# Bidirectional_Amp.net
KiCad netlist of a schematic drawn in EAGLE
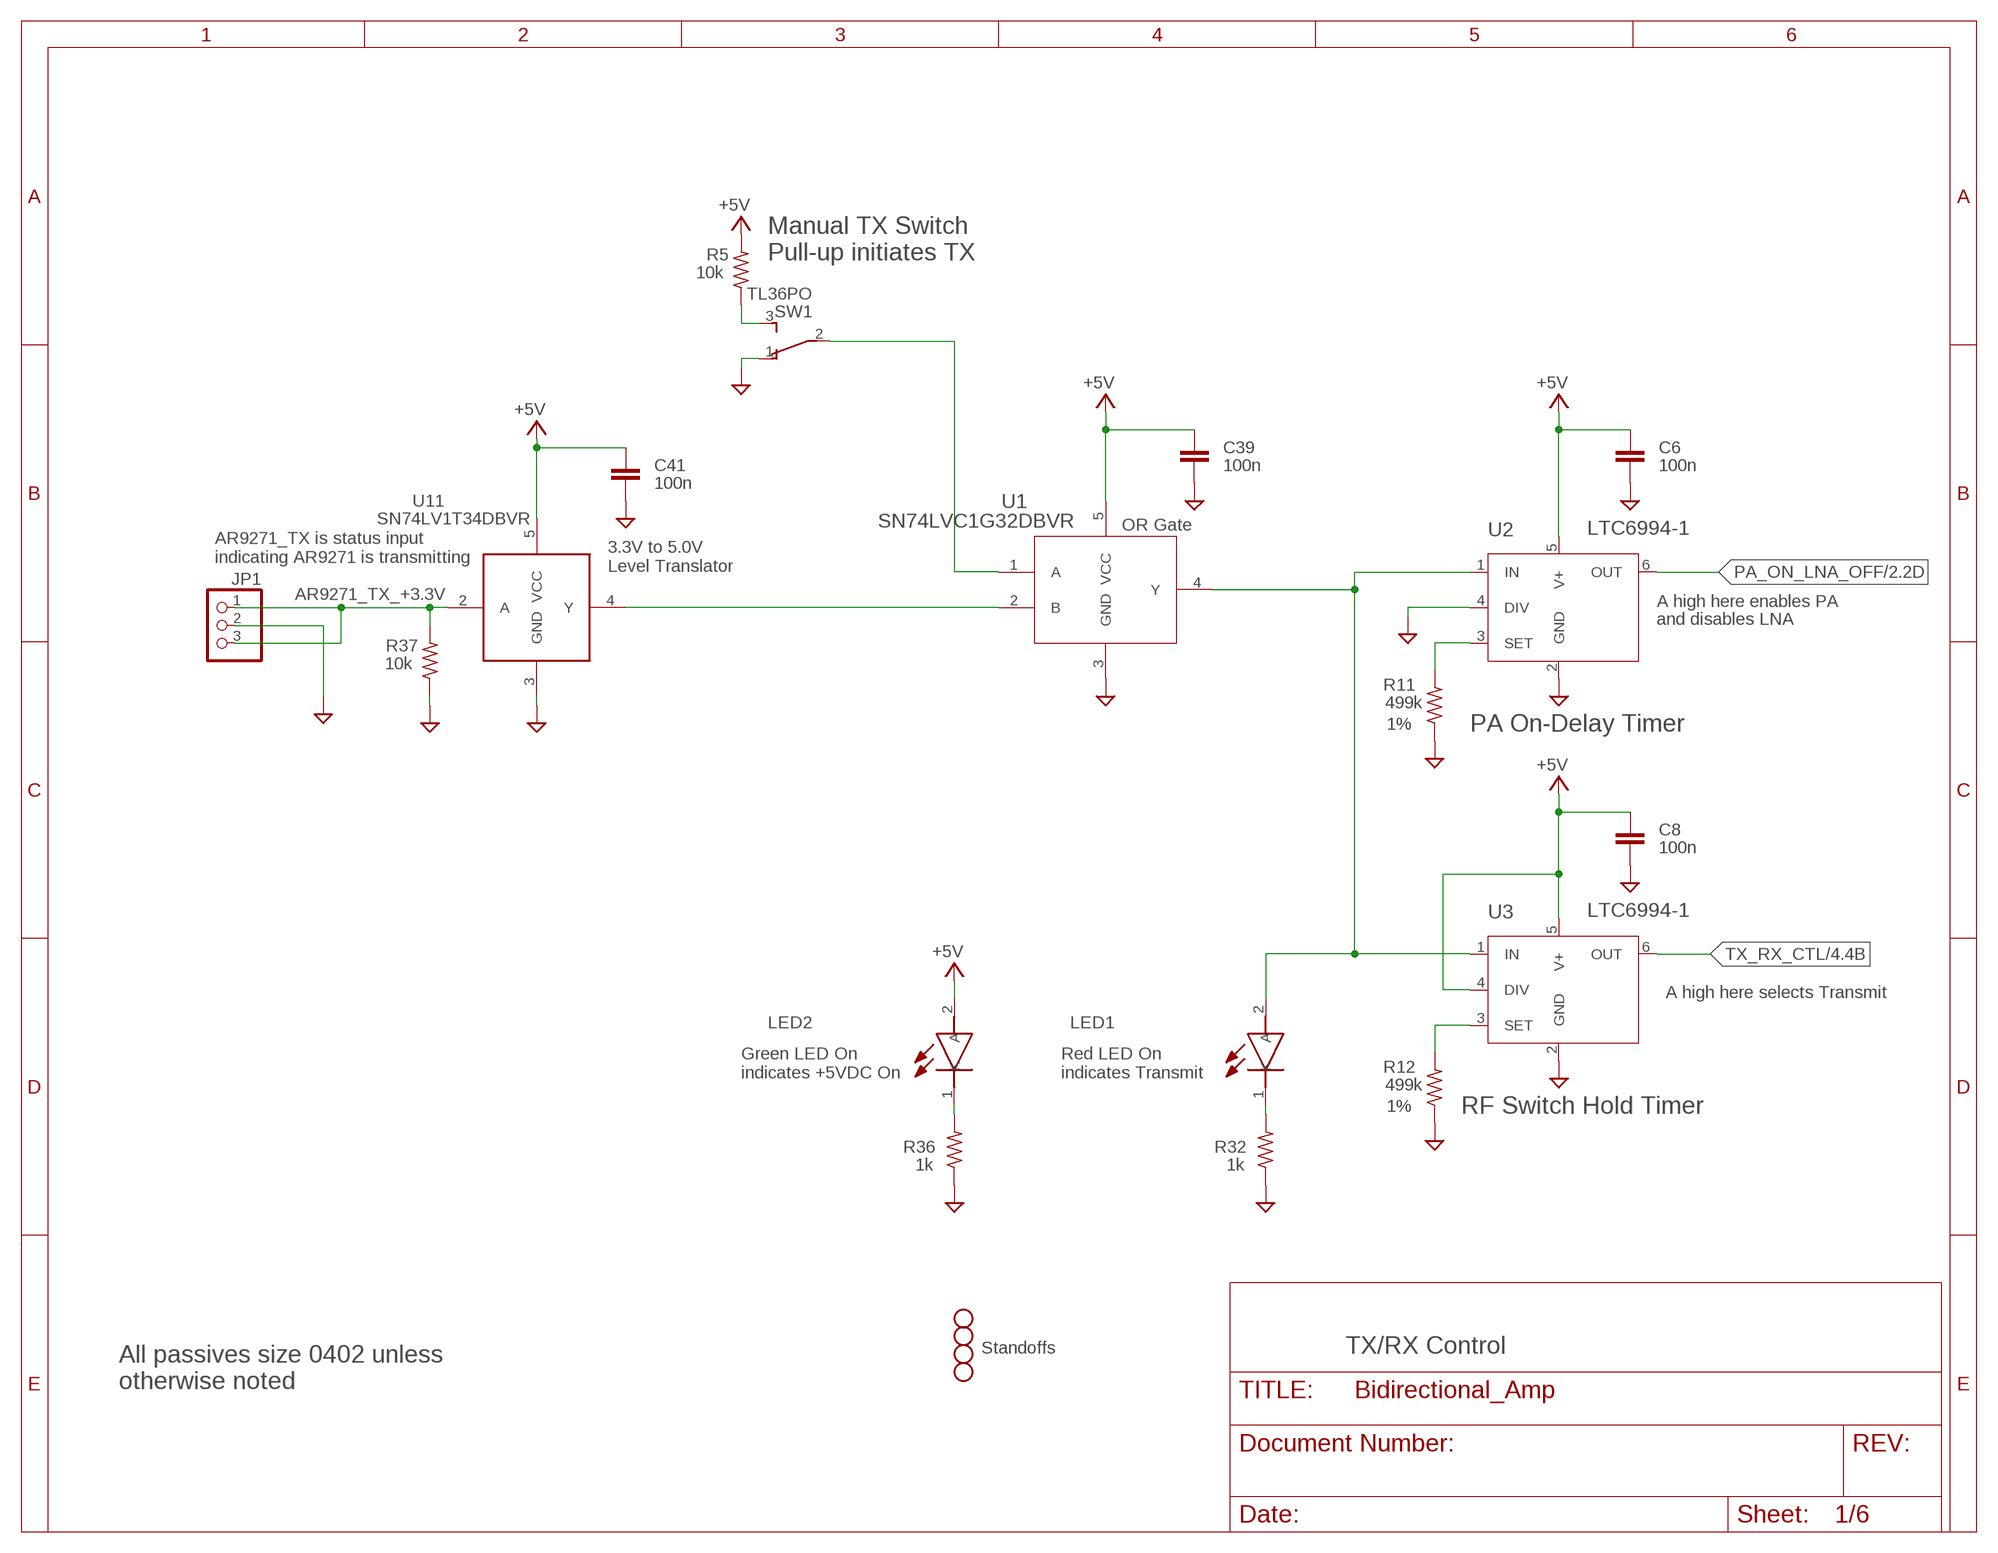
[diagram p0: schematic, sheet 1]
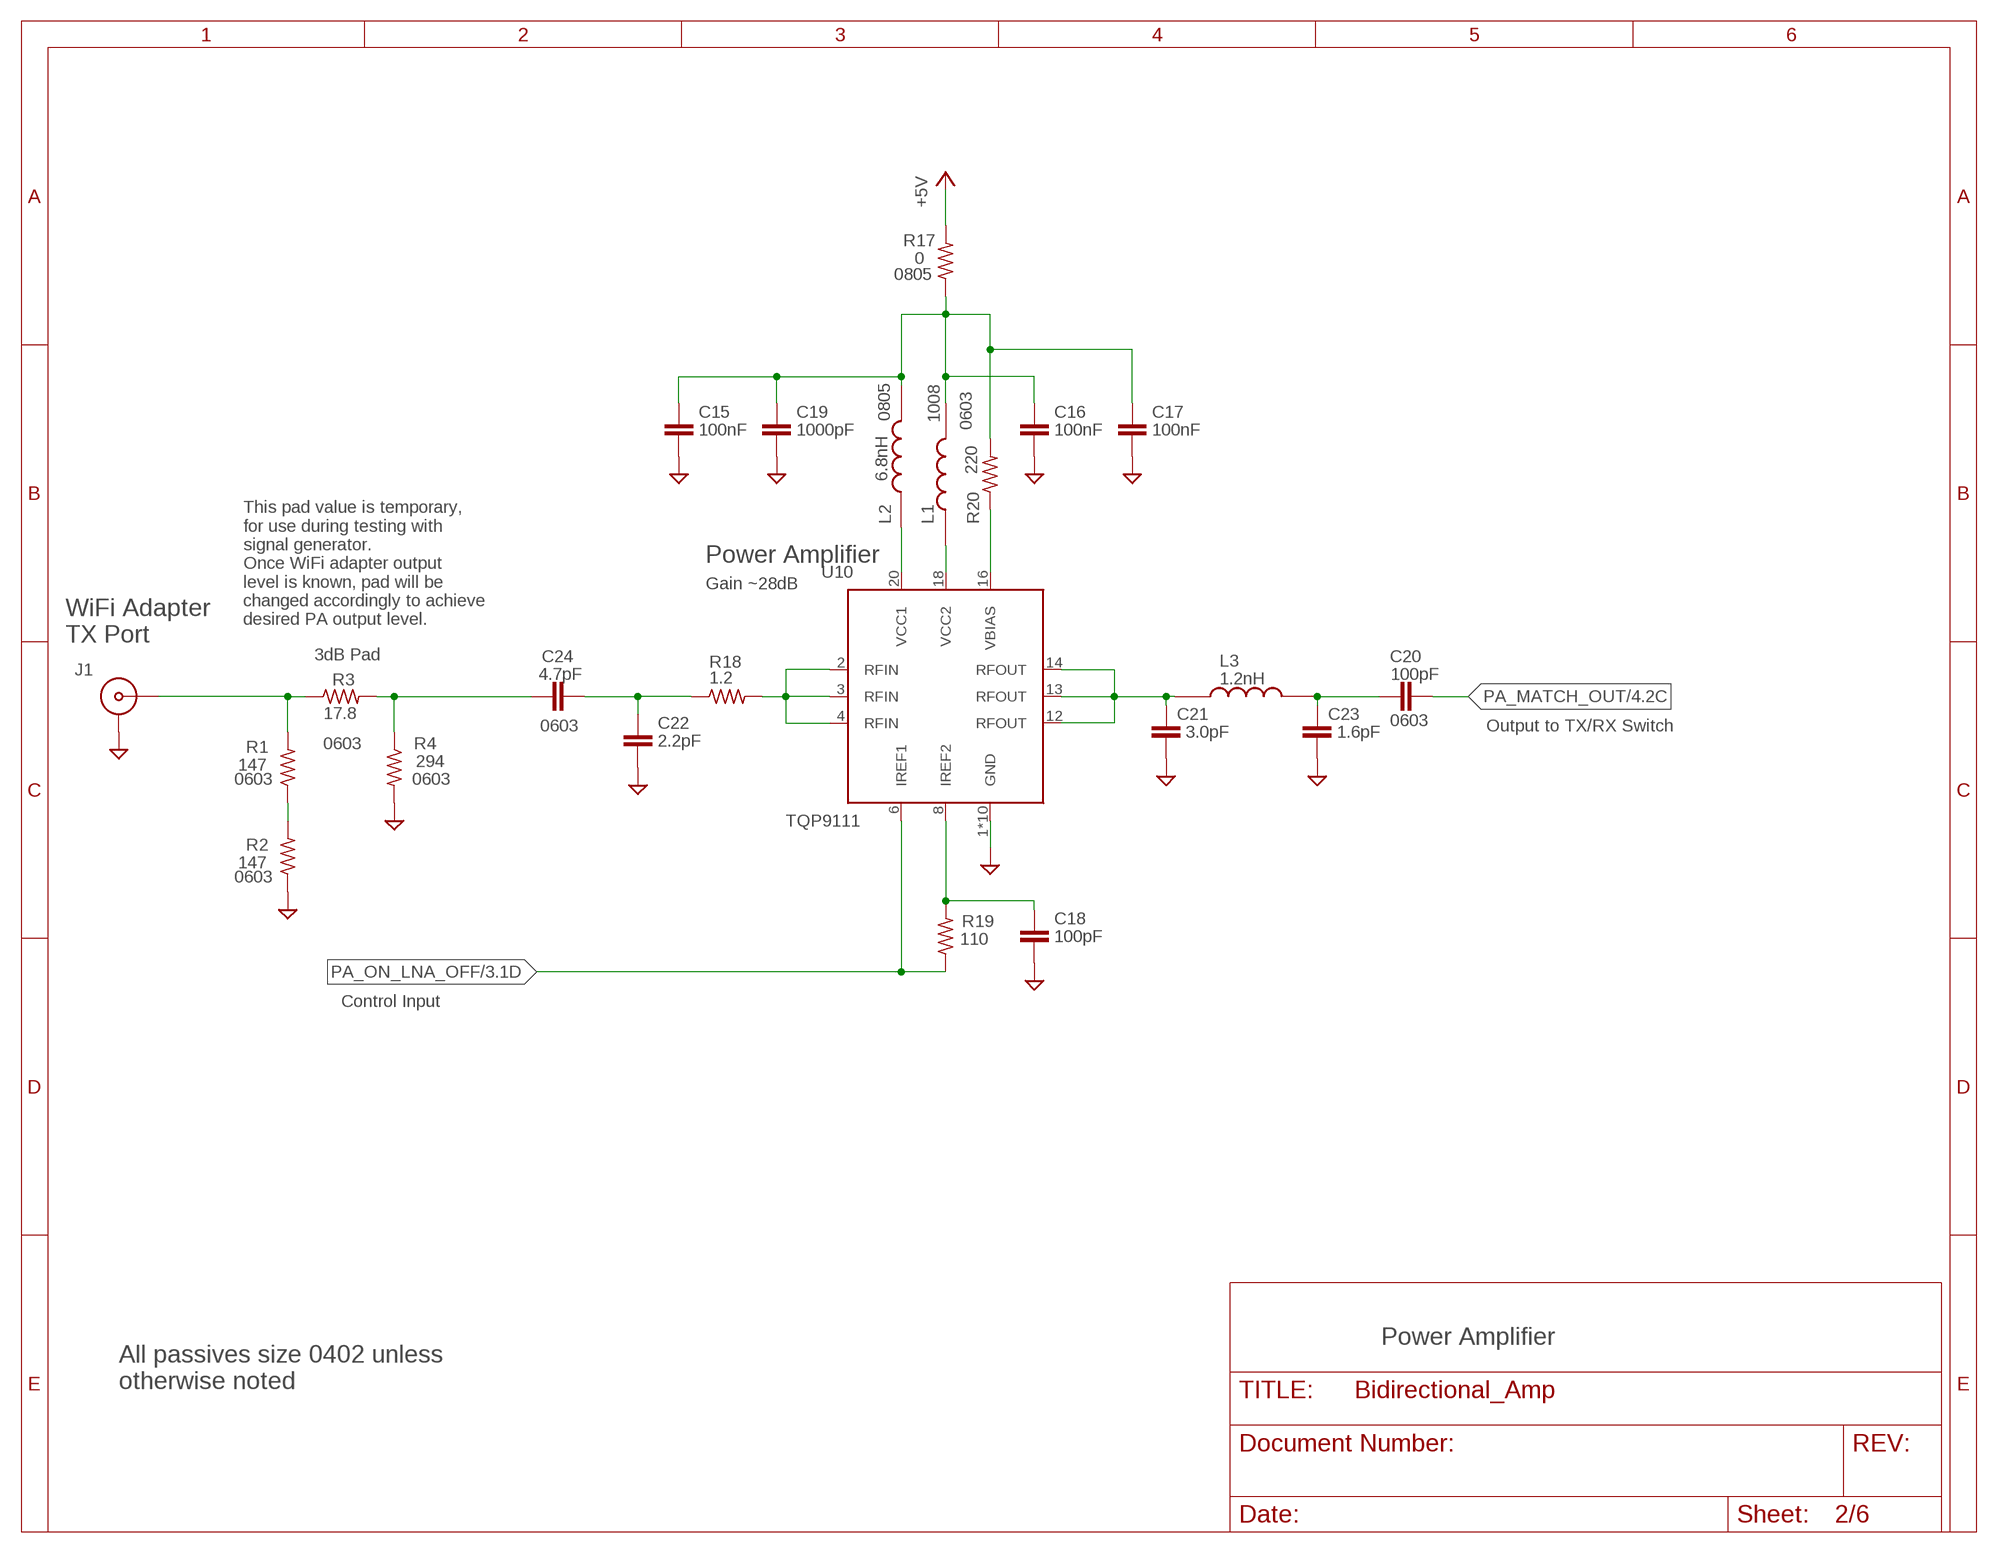
[diagram p1: schematic, sheet 2]
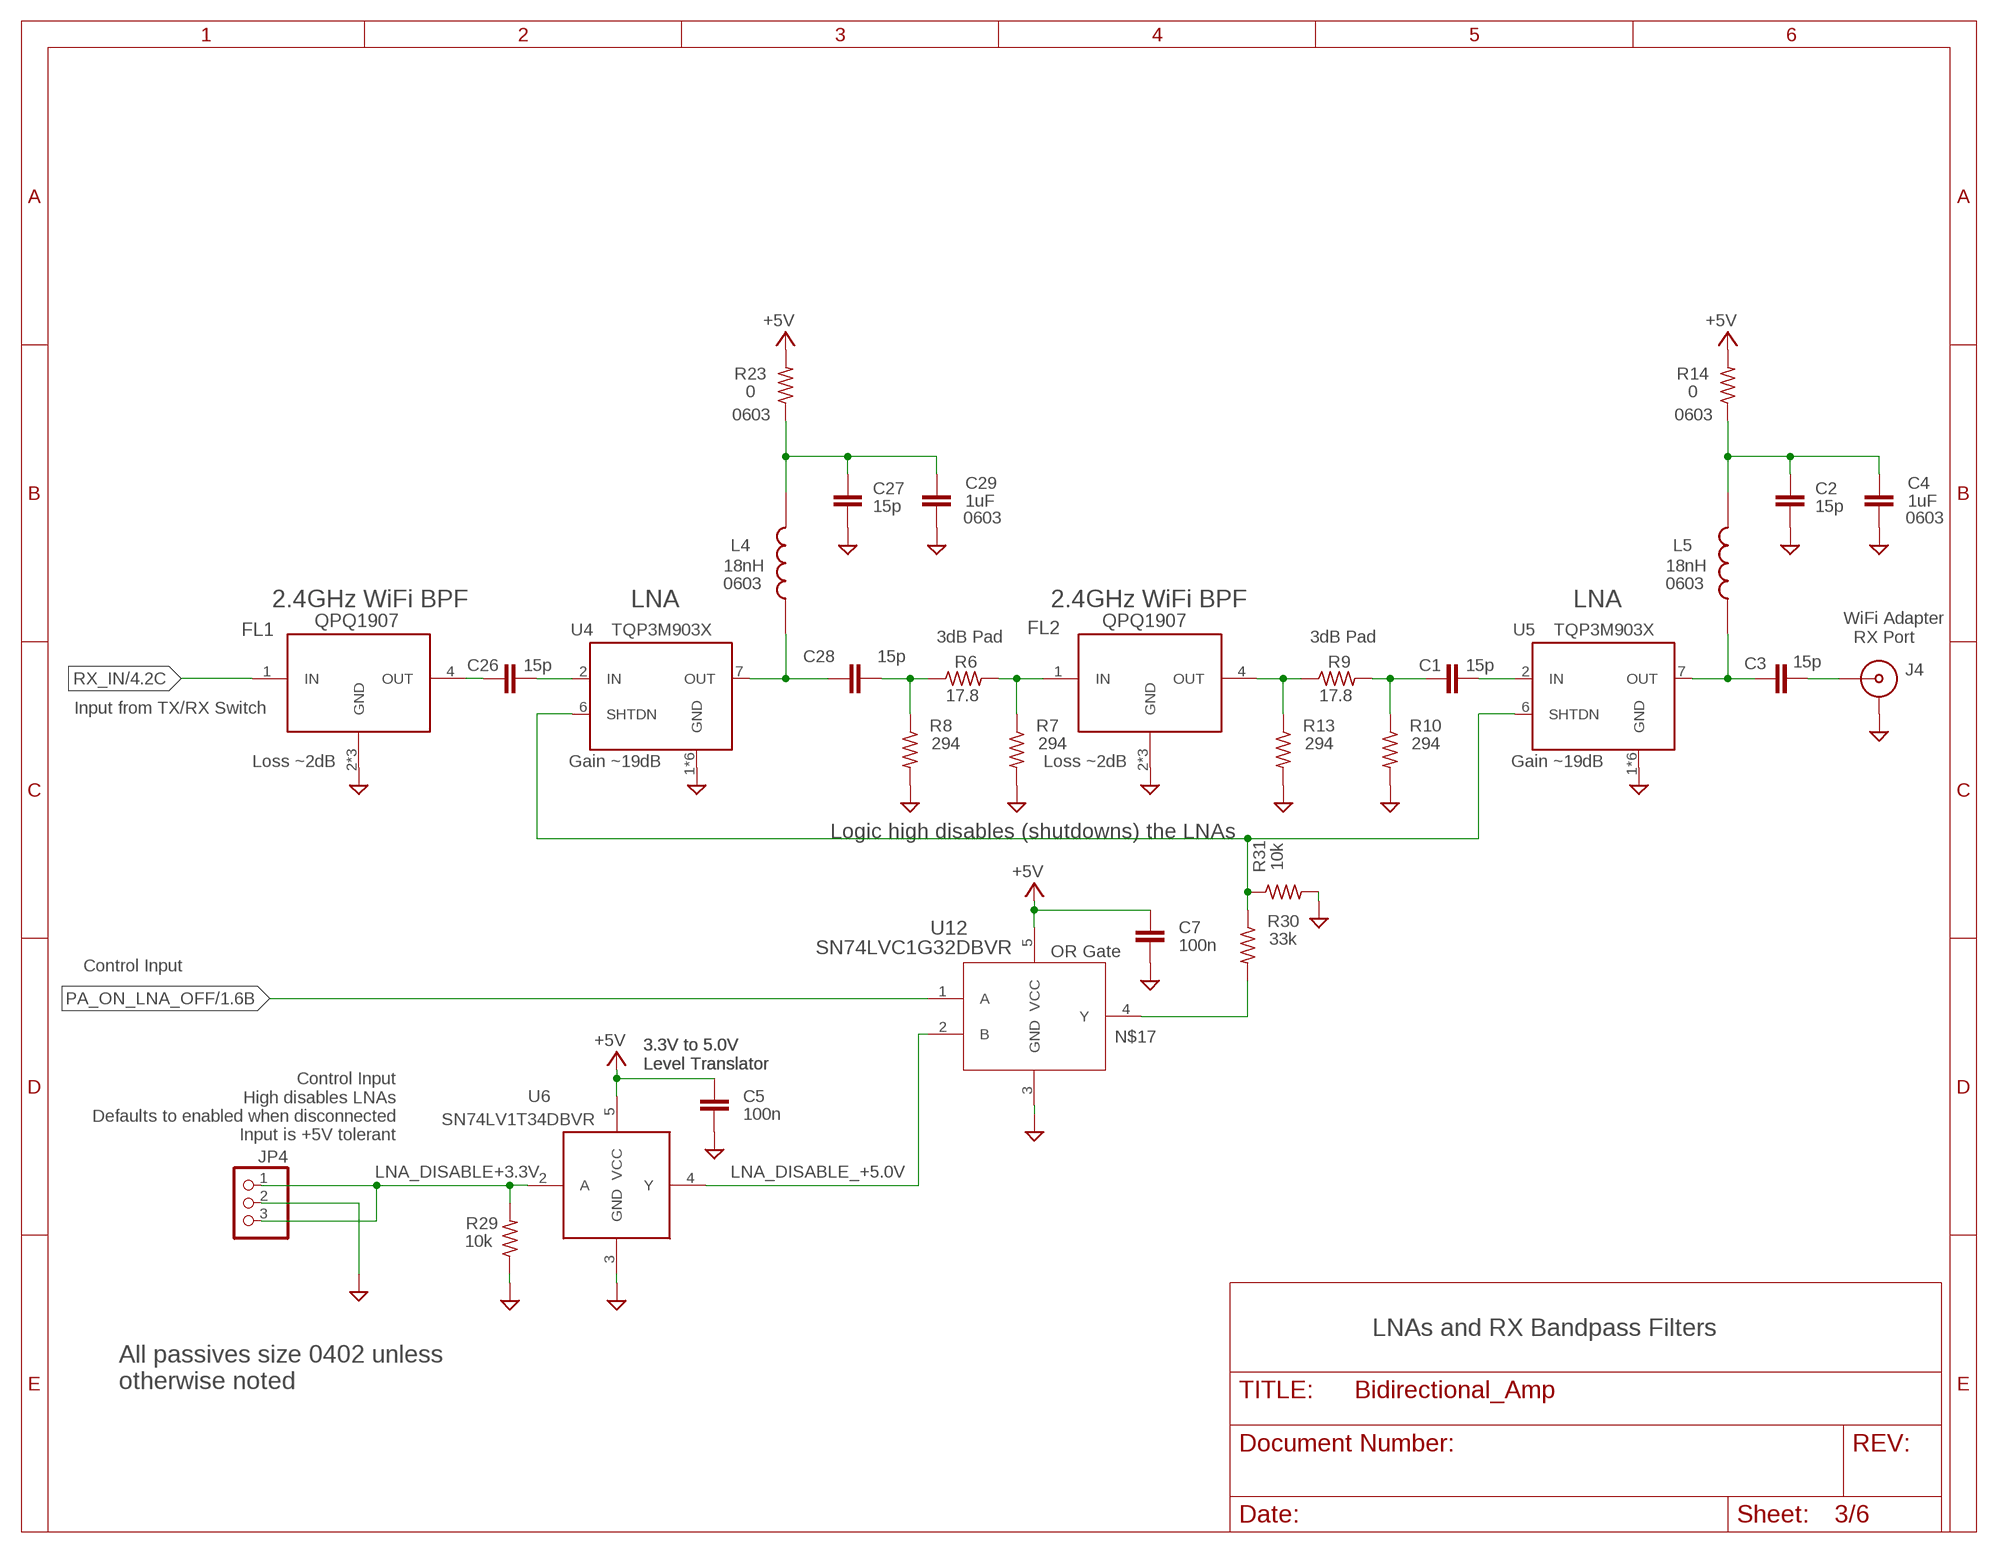
[diagram p2: schematic, sheet 3]
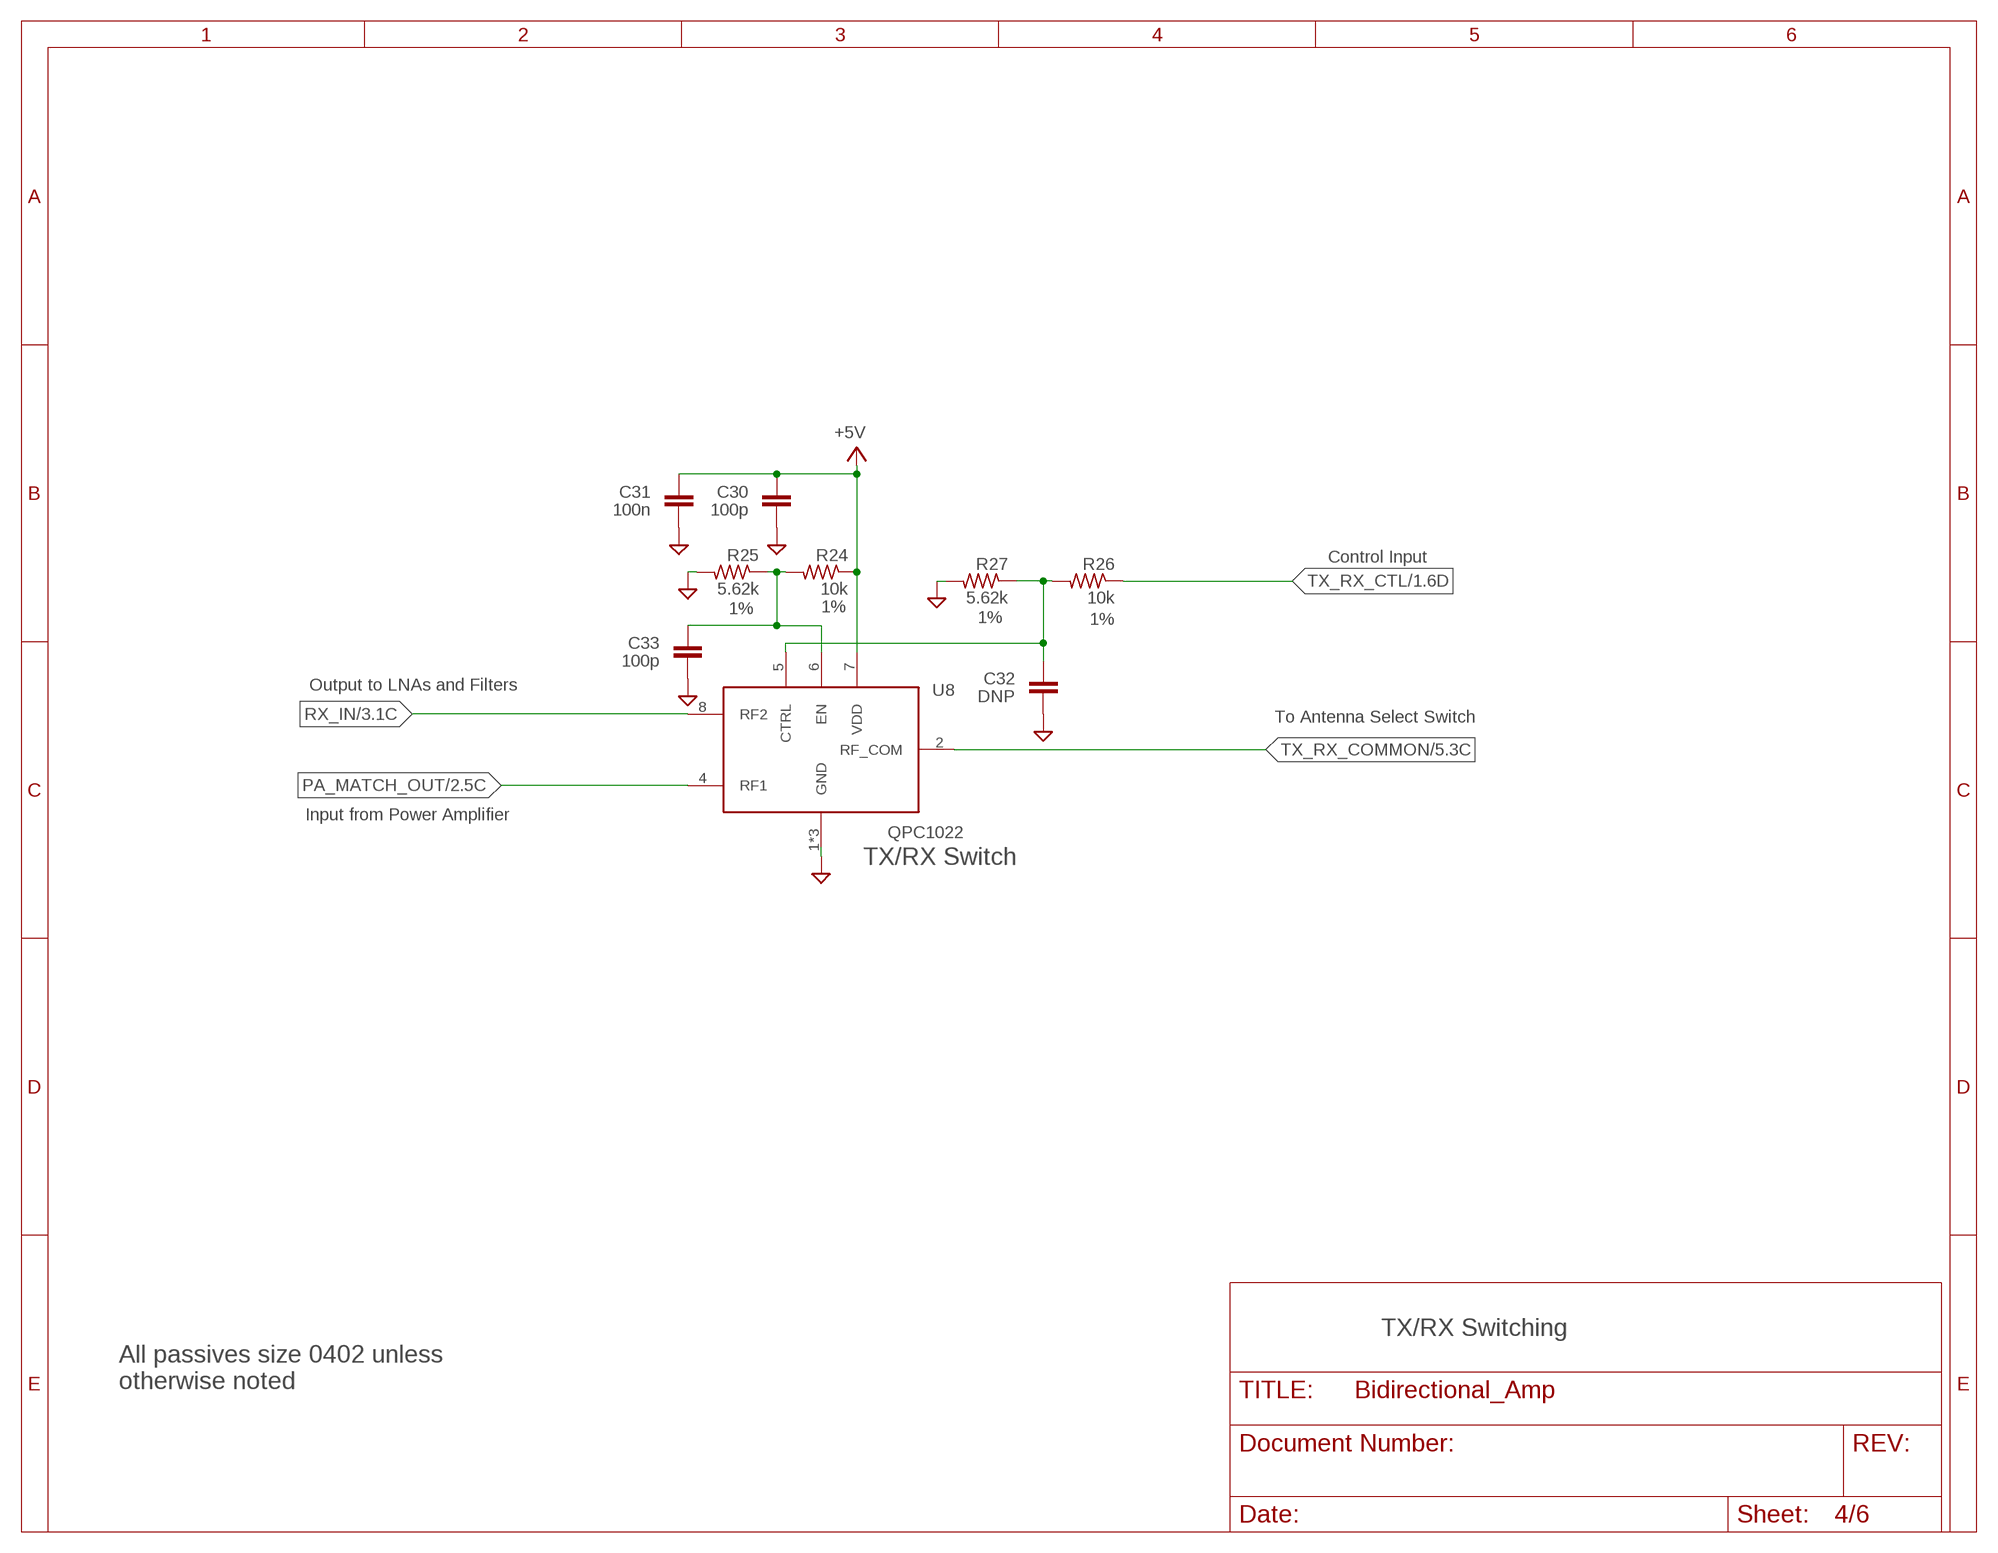
[diagram p3: schematic, sheet 4]
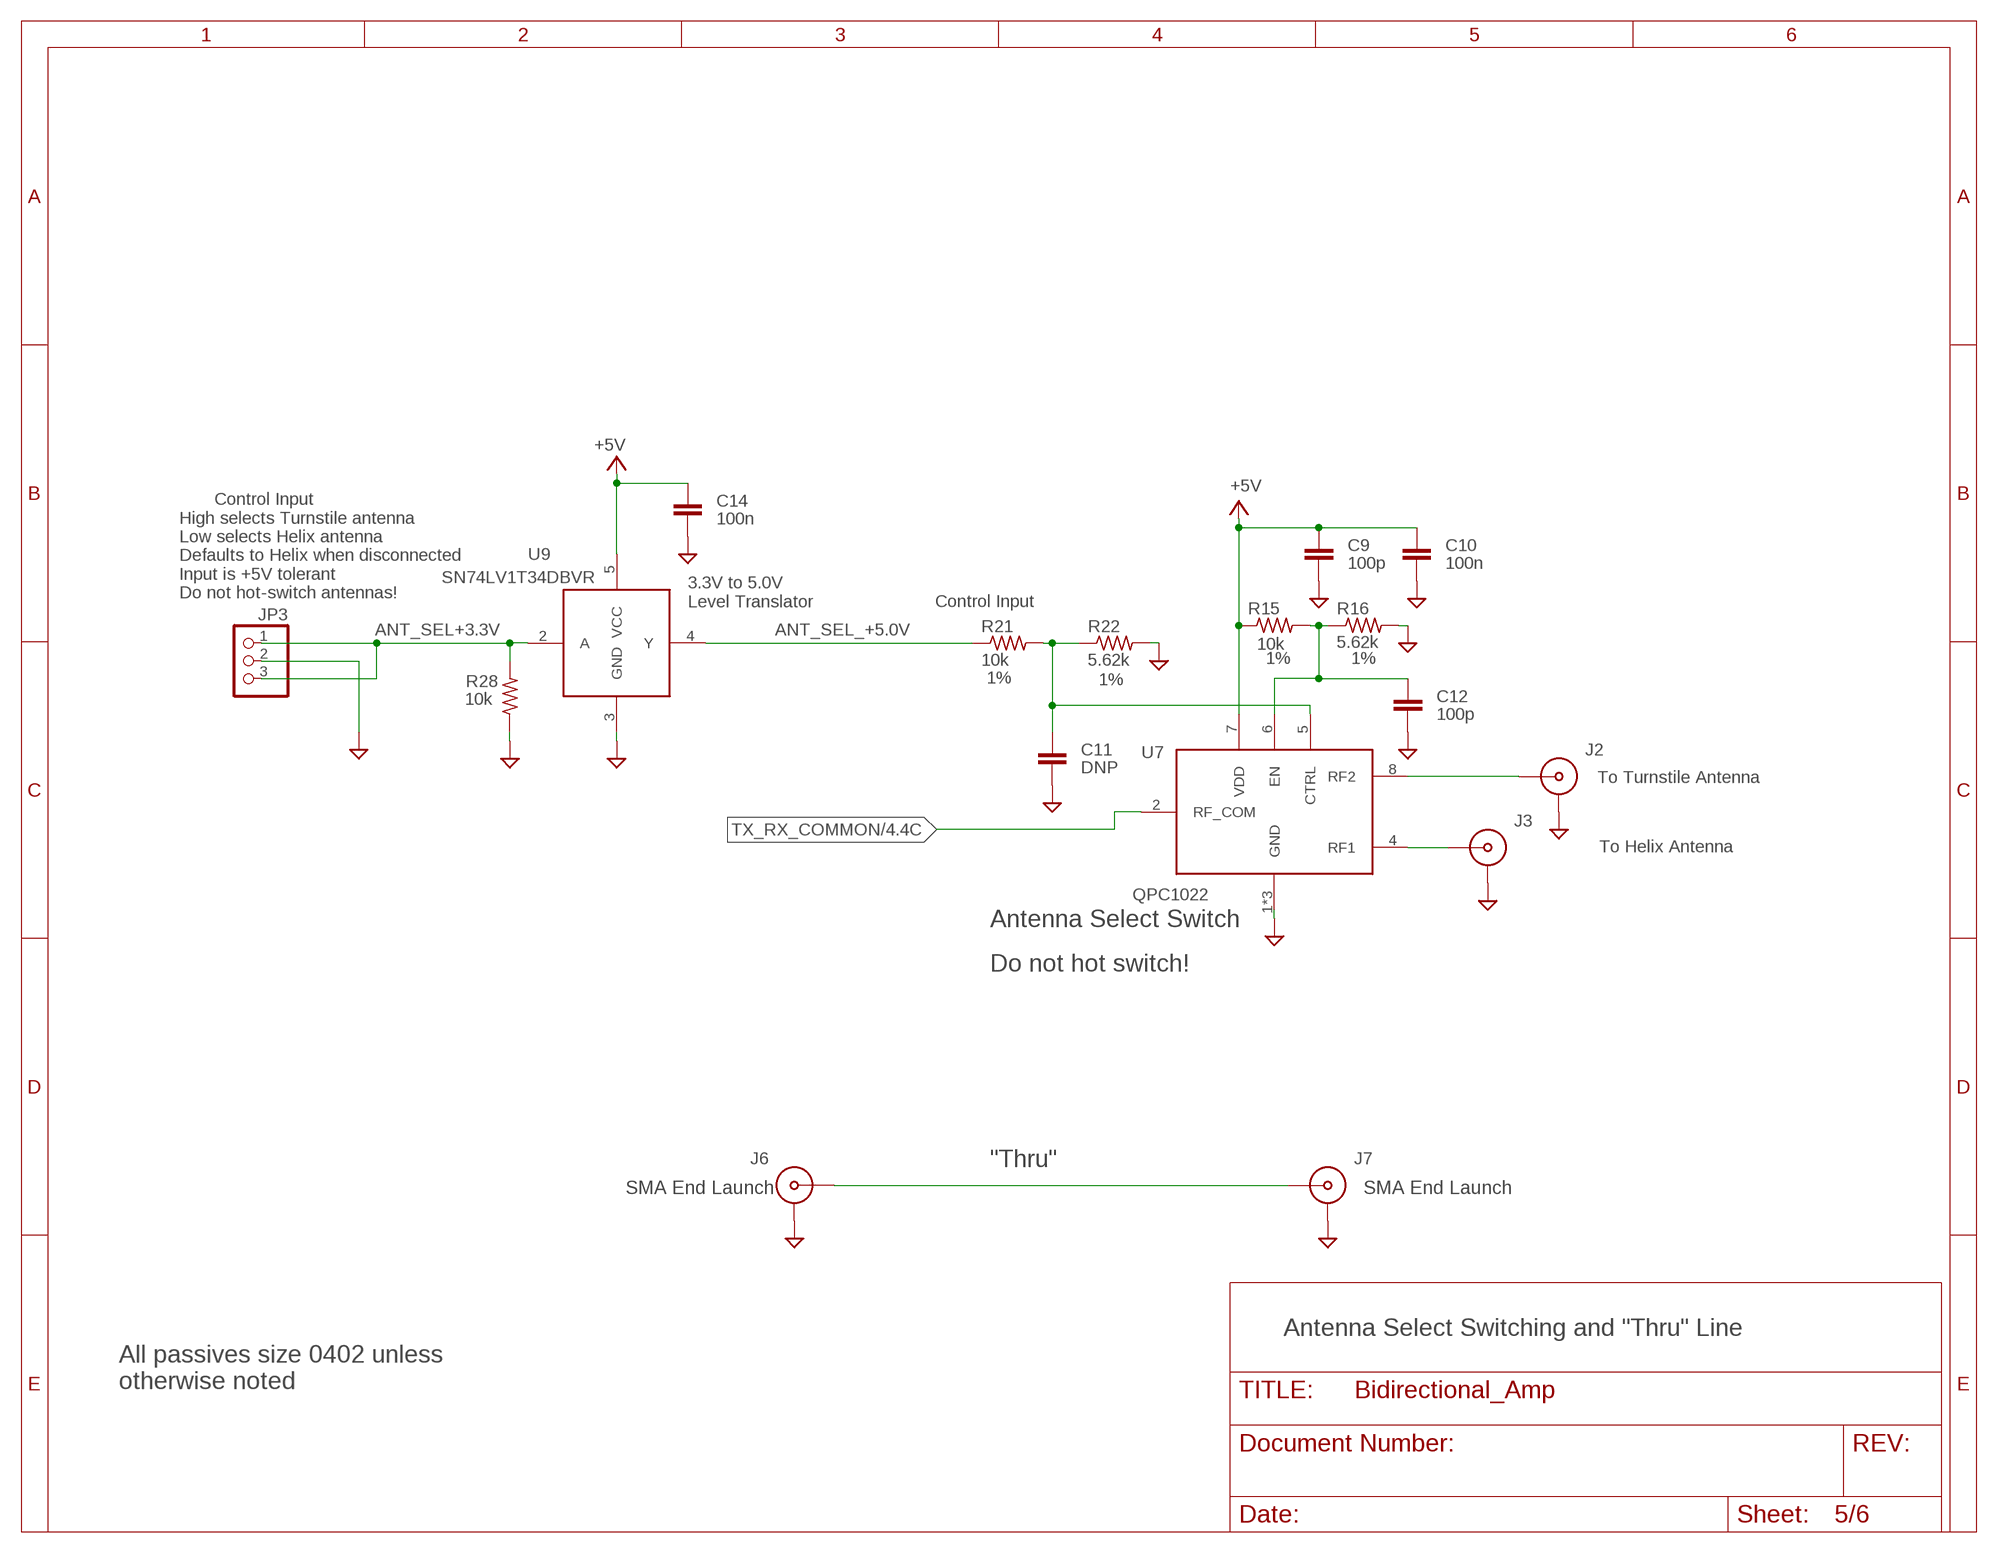
[diagram p4: schematic, sheet 5]
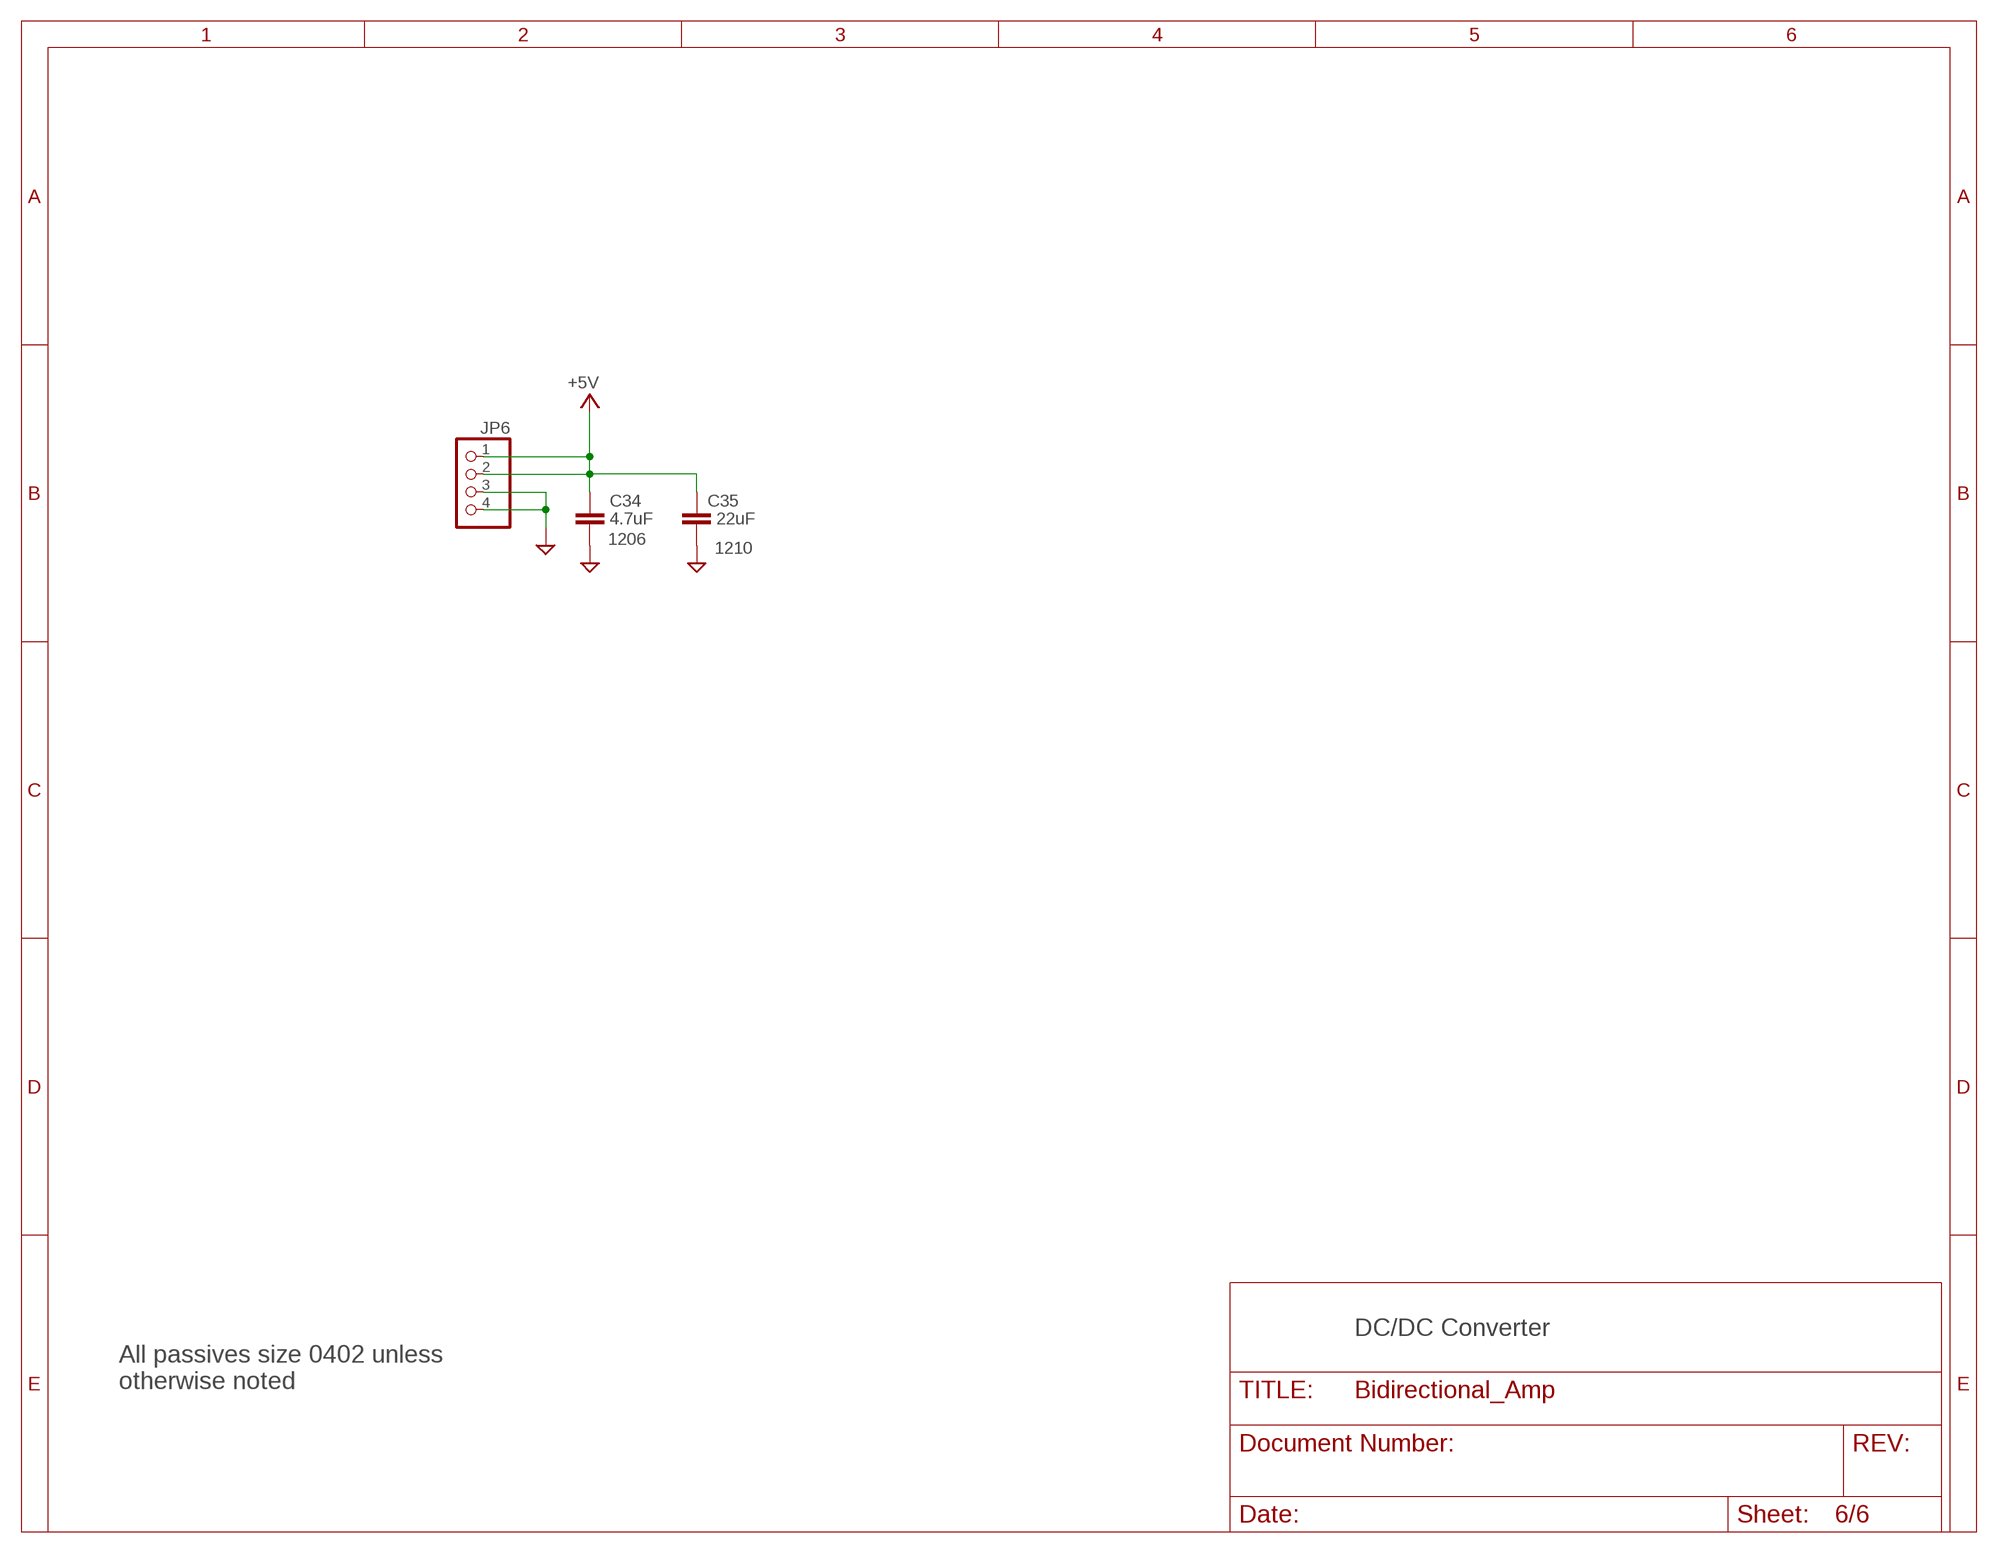
[diagram p5: schematic, sheet 6]

(export (version "E")
  (design (tool "Eeschema 10.0.6"))
  (components
    (comp (ref "C6")
      (value "100n")
      (footprint "eagle-import:.0402-B-NOSILK")
      (fields (field (name "MFR") "TDK") (field (name "MPN") "CGA2B1X7R1C104K050BC"))
      (libsource (lib "eagle-import") (part "C-EU0402-B-NOSILK"))
    )
    (comp (ref "C8")
      (value "100n")
      (footprint "eagle-import:.0402-B-NOSILK")
      (fields (field (name "MFR") "TDK") (field (name "MPN") "CGA2B1X7R1C104K050BC"))
      (libsource (lib "eagle-import") (part "C-EU0402-B-NOSILK"))
    )
    (comp (ref "C39")
      (value "100n")
      (footprint "eagle-import:.0402-B-NOSILK")
      (fields (field (name "MFR") "TDK") (field (name "MPN") "CGA2B1X7R1C104K050BC"))
      (libsource (lib "eagle-import") (part "C-EU0402-B-NOSILK"))
    )
    (comp (ref "C41")
      (value "100n")
      (footprint "eagle-import:.0402-B-NOSILK")
      (fields (field (name "MFR") "TDK") (field (name "MPN") "CGA2B1X7R1C104K050BC"))
      (libsource (lib "eagle-import") (part "C-EU0402-B-NOSILK"))
    )
    (comp (ref "H1")
      (value "STAND-OFFTIGHT")
      (footprint "eagle-import:STAND-OFF-TIGHT")
      (libsource (lib "eagle-import") (part "STAND-OFFTIGHT"))
    )
    (comp (ref "H2")
      (value "STAND-OFFTIGHT")
      (footprint "eagle-import:STAND-OFF-TIGHT")
      (libsource (lib "eagle-import") (part "STAND-OFFTIGHT"))
    )
    (comp (ref "H3")
      (value "STAND-OFFTIGHT")
      (footprint "eagle-import:STAND-OFF-TIGHT")
      (libsource (lib "eagle-import") (part "STAND-OFFTIGHT"))
    )
    (comp (ref "H4")
      (value "STAND-OFFTIGHT")
      (footprint "eagle-import:STAND-OFF-TIGHT")
      (libsource (lib "eagle-import") (part "STAND-OFFTIGHT"))
    )
    (comp (ref "JP1")
      (value "PINHD-1X3")
      (footprint "eagle-import:1X03")
      (fields (field (name "MFR") "Molex") (field (name "MPN") "22-23-2031"))
      (libsource (lib "eagle-import") (part "PINHD-1X3"))
    )
    (comp (ref "LED1")
      (value "LTST-C193KRKT-5A")
      (footprint "eagle-import:LEDC1607X80N")
      (fields (field (name "MFR") "Lite-On"))
      (libsource (lib "eagle-import") (part "LTST-C193KRKT-5A"))
    )
    (comp (ref "LED2")
      (value "LTST-C193KGKT-5A")
      (footprint "eagle-import:LEDC1607X80N")
      (fields (field (name "MFR") "Lite-On"))
      (libsource (lib "eagle-import") (part "LTST-C193KGKT-5A"))
    )
    (comp (ref "R5")
      (value "10k")
      (footprint "eagle-import:.0402-B-NOSILK")
      (fields (field (name "MFR") "Panasonic") (field (name "MPN") "ERJ-2GEJ103X"))
      (libsource (lib "eagle-import") (part "R-US_0402-B-NOSILK"))
    )
    (comp (ref "R11")
      (value "499k")
      (footprint "eagle-import:.0402-B-NOSILK")
      (fields (field (name "MFR") "Panasonic") (field (name "MPN") "ERJ-2RKF4993X"))
      (libsource (lib "eagle-import") (part "R-US_0402-B-NOSILK"))
    )
    (comp (ref "R12")
      (value "499k")
      (footprint "eagle-import:.0402-B-NOSILK")
      (fields (field (name "MFR") "Panasonic") (field (name "MPN") "ERJ-2RKF4993X"))
      (libsource (lib "eagle-import") (part "R-US_0402-B-NOSILK"))
    )
    (comp (ref "R32")
      (value "1k")
      (footprint "eagle-import:.0402-B-NOSILK")
      (fields (field (name "MFR") "Panasonic") (field (name "MPN") "ERJ-2GEJ102X"))
      (libsource (lib "eagle-import") (part "R-US_0402-B-NOSILK"))
    )
    (comp (ref "R36")
      (value "1k")
      (footprint "eagle-import:.0402-B-NOSILK")
      (fields (field (name "MFR") "Panasonic") (field (name "MPN") "ERJ-2GEJ102X"))
      (libsource (lib "eagle-import") (part "R-US_0402-B-NOSILK"))
    )
    (comp (ref "R37")
      (value "10k")
      (footprint "eagle-import:.0402-B-NOSILK")
      (fields (field (name "MFR") "Panasonic") (field (name "MPN") "ERJ-2GEJ103X"))
      (libsource (lib "eagle-import") (part "R-US_0402-B-NOSILK"))
    )
    (comp (ref "SW1")
      (value "TL36PO")
      (footprint "eagle-import:TL3XPO")
      (fields (field (name "MFR") "APEM Inc.") (field (name "MPN") "TL36P005000"))
      (libsource (lib "eagle-import") (part "TL36PO"))
    )
    (comp (ref "U1")
      (value "SN74LVC1G32DBVR")
      (footprint "eagle-import:DBV5")
      (fields (field (name "MFR") "Texas Instruments"))
      (libsource (lib "eagle-import") (part "SN74LVC1G32DBVR"))
    )
    (comp (ref "U2")
      (value "LTC6994-1")
      (footprint "eagle-import:TSOT-23_S6")
      (fields (field (name "MFR") "Linear Technology"))
      (libsource (lib "eagle-import") (part "LTC6994CS6-1PBF"))
    )
    (comp (ref "U3")
      (value "LTC6994-1")
      (footprint "eagle-import:TSOT-23_S6")
      (fields (field (name "MFR") "Linear Technology"))
      (libsource (lib "eagle-import") (part "LTC6994CS6-1PBF"))
    )
    (comp (ref "U11")
      (value "SN74LV1T34DBVR")
      (footprint "eagle-import:SOT95P280X145-5N")
      (fields (field (name "MFR") "Texas Instruments"))
      (libsource (lib "eagle-import") (part "SN74LV1T34DBVR"))
    )
    (comp (ref "C9")
      (value "100p")
      (footprint "eagle-import:.0402-B-NOSILK")
      (fields (field (name "MFR") "Murata") (field (name "MPN") "GCM1555C1H101JA16D "))
      (libsource (lib "eagle-import") (part "C-EU0402-B-NOSILK"))
    )
    (comp (ref "C10")
      (value "100n")
      (footprint "eagle-import:.0402-B-NOSILK")
      (fields (field (name "MFR") "TDK Corporation") (field (name "MPN") "CGA2B1X7R1C104K050BC"))
      (libsource (lib "eagle-import") (part "C-EU0402-B-NOSILK"))
    )
    (comp (ref "C11")
      (value "DNP")
      (footprint "eagle-import:.0402-B-NOSILK")
      (fields (field (name "MPN") "GCM1555C1H101JA16D "))
      (libsource (lib "eagle-import") (part "C-EU0402-B-NOSILK"))
    )
    (comp (ref "C12")
      (value "100p")
      (footprint "eagle-import:.0402-B-NOSILK")
      (fields (field (name "MPN") "GCM1555C1H101JA16D "))
      (libsource (lib "eagle-import") (part "C-EU0402-B-NOSILK"))
    )
    (comp (ref "C14")
      (value "100n")
      (footprint "eagle-import:.0402-B-NOSILK")
      (fields (field (name "MFR") "TDK Corporation") (field (name "MPN") "CGA2B1X7R1C104K050BC"))
      (libsource (lib "eagle-import") (part "C-EU0402-B-NOSILK"))
    )
    (comp (ref "J2")
      (value "142-0701-851_ALT")
      (footprint "eagle-import:142-0701-851")
      (fields (field (name "MFR") "Cinch") (field (name "MPN") "142-0701-851"))
      (libsource (lib "eagle-import") (part "142-0701-851_ALT"))
    )
    (comp (ref "J3")
      (value "142-0701-851_ALT")
      (footprint "eagle-import:142-0701-851")
      (fields (field (name "MFR") "Cinch") (field (name "MPN") "142-0701-851"))
      (libsource (lib "eagle-import") (part "142-0701-851_ALT"))
    )
    (comp (ref "J6")
      (value "142-0701-851_ALT")
      (footprint "eagle-import:142-0701-851")
      (fields (field (name "MFR") "Cinch") (field (name "MPN") "142-0701-851"))
      (libsource (lib "eagle-import") (part "142-0701-851_ALT"))
    )
    (comp (ref "J7")
      (value "142-0701-851_ALT")
      (footprint "eagle-import:142-0701-851")
      (fields (field (name "MFR") "Cinch") (field (name "MPN") "142-0701-851"))
      (libsource (lib "eagle-import") (part "142-0701-851_ALT"))
    )
    (comp (ref "JP3")
      (value "PINHD-1X3")
      (footprint "eagle-import:1X03")
      (fields (field (name "MFR") "Molex") (field (name "MPN") "22-23-2031"))
      (libsource (lib "eagle-import") (part "PINHD-1X3"))
    )
    (comp (ref "R15")
      (value "10k")
      (footprint "eagle-import:.0402-B-NOSILK")
      (fields (field (name "MFR") "Panasonic") (field (name "MPN") "ERJ-2RKF1002X"))
      (libsource (lib "eagle-import") (part "R-US_0402-B-NOSILK"))
    )
    (comp (ref "R16")
      (value "5.62k")
      (footprint "eagle-import:.0402-B-NOSILK")
      (fields (field (name "MFR") "Panasonic") (field (name "MPN") "ERJ-2RKF5621X"))
      (libsource (lib "eagle-import") (part "R-US_0402-B-NOSILK"))
    )
    (comp (ref "R21")
      (value "10k")
      (footprint "eagle-import:.0402-B-NOSILK")
      (fields (field (name "MFR") "Panasonic") (field (name "MPN") "ERJ-2RKF1002X"))
      (libsource (lib "eagle-import") (part "R-US_0402-B-NOSILK"))
    )
    (comp (ref "R22")
      (value "5.62k")
      (footprint "eagle-import:.0402-B-NOSILK")
      (fields (field (name "MFR") "Panasonic") (field (name "MPN") "ERJ-2RKF5621X"))
      (libsource (lib "eagle-import") (part "R-US_0402-B-NOSILK"))
    )
    (comp (ref "R28")
      (value "10k")
      (footprint "eagle-import:.0402-B-NOSILK")
      (fields (field (name "MFR") "Panasonic") (field (name "MPN") "ERJ-2GEJ103X"))
      (libsource (lib "eagle-import") (part "R-US_0402-B-NOSILK"))
    )
    (comp (ref "U7")
      (value "QPC1022")
      (footprint "eagle-import:QPC1022")
      (fields (field (name "MFR") "Qorvo"))
      (libsource (lib "eagle-import") (part "QPC1022"))
    )
    (comp (ref "U9")
      (value "SN74LV1T34DBVR")
      (footprint "eagle-import:SOT95P280X145-5N")
      (fields (field (name "MFR") "Texas Instruments"))
      (libsource (lib "eagle-import") (part "SN74LV1T34DBVR"))
    )
    (comp (ref "C15")
      (value "100nF")
      (footprint "eagle-import:.0402-B-NOSILK")
      (fields (field (name "MFR") "TDK") (field (name "MPN") "CGA2B1X7R1C104K050BC"))
      (libsource (lib "eagle-import") (part "C-EU0402-B-NOSILK"))
    )
    (comp (ref "C16")
      (value "100nF")
      (footprint "eagle-import:.0402-B-NOSILK")
      (fields (field (name "MFR") "TDK") (field (name "MPN") "CGA2B1X7R1C104K050BC"))
      (libsource (lib "eagle-import") (part "C-EU0402-B-NOSILK"))
    )
    (comp (ref "C17")
      (value "100nF")
      (footprint "eagle-import:.0402-B-NOSILK")
      (fields (field (name "MFR") "TDK") (field (name "MPN") "CGA2B1X7R1C104K050BC"))
      (libsource (lib "eagle-import") (part "C-EU0402-B-NOSILK"))
    )
    (comp (ref "C18")
      (value "100pF")
      (footprint "eagle-import:.0402-B-NOSILK")
      (fields (field (name "MFR") "Murata") (field (name "MPN") "GCM1555C1H101JA16D"))
      (libsource (lib "eagle-import") (part "C-EU0402-B-NOSILK"))
    )
    (comp (ref "C19")
      (value "1000pF")
      (footprint "eagle-import:.0402-B-NOSILK")
      (fields (field (name "MFR") "TDK") (field (name "MPN") "CGA2B2NP01H102J050BA"))
      (libsource (lib "eagle-import") (part "C-EU0402-B-NOSILK"))
    )
    (comp (ref "C20")
      (value "100pF")
      (footprint "eagle-import:.0603-C-NOSILK")
      (fields (field (name "MFR") "Murata") (field (name "MPN") "GCM1885C1H101JA16D "))
      (libsource (lib "eagle-import") (part "C-EU0603-C-NOSILK"))
    )
    (comp (ref "C21")
      (value "3.0pF")
      (footprint "eagle-import:.0402-C-NOSILK")
      (fields (field (name "MFR") "Taiyo Yuden") (field (name "MPN") "UVK105CG030JW-F"))
      (libsource (lib "eagle-import") (part "C-EU0402-C-NOSILK"))
    )
    (comp (ref "C22")
      (value "2.2pF")
      (footprint "eagle-import:.0402-C-NOSILK")
      (fields (field (name "MFR") "Taiyo Yuden") (field (name "MPN") "UVK105CG2R2JW-F"))
      (libsource (lib "eagle-import") (part "C-EU0402-C-NOSILK"))
    )
    (comp (ref "C23")
      (value "1.6pF")
      (footprint "eagle-import:.0402-C-NOSILK")
      (fields (field (name "MFR") "Murata") (field (name "MPN") "GJM1555C1H1R6BB01D"))
      (libsource (lib "eagle-import") (part "C-EU0402-C-NOSILK"))
    )
    (comp (ref "C24")
      (value "4.7pF")
      (footprint "eagle-import:.0603-C-NOSILK")
      (fields (field (name "MFR") "AVX Corp.") (field (name "MPN") "06032U4R7BAT2A "))
      (libsource (lib "eagle-import") (part "C-EU0603-C-NOSILK"))
    )
    (comp (ref "J1")
      (value "142-0701-851_ALT")
      (footprint "eagle-import:142-0701-851")
      (fields (field (name "MFR") "Cinch") (field (name "MPN") "142-0701-851"))
      (libsource (lib "eagle-import") (part "142-0701-851_ALT"))
    )
    (comp (ref "L1")
      (value "1008HQ-10NXJLB1008_IMPERIAL_2520_METRIC")
      (footprint "eagle-import:INDC2520X120N")
      (fields (field (name "MFR") "COILCRAFT") (field (name "MPN") "1008HQ-10NXJLB"))
      (libsource (lib "eagle-import") (part "1008HQ-10NXJLB1008_IMPERIAL_2520_METRIC"))
    )
    (comp (ref "L2")
      (value "6.8nH")
      (footprint "eagle-import:0805CS")
      (fields (field (name "MFR") "COILCRAFT") (field (name "MPN") "0805CS-060XJLC"))
      (libsource (lib "eagle-import") (part "0805CS-060XJLC"))
    )
    (comp (ref "L3")
      (value "1.2nH")
      (footprint "eagle-import:0402CS1N2XJLW")
      (fields (field (name "MFR") "COILCRAFT") (field (name "MPN") "0402CS-1N2XJLW"))
      (libsource (lib "eagle-import") (part "0402CS-1N2XJLW"))
    )
    (comp (ref "R1")
      (value "147")
      (footprint "eagle-import:.0603-C-NOSILK")
      (fields (field (name "MFR") "Panasonic") (field (name "MPN") "ERJ-3EKF1470V"))
      (libsource (lib "eagle-import") (part "R-US_0603-C-NOSILK"))
    )
    (comp (ref "R2")
      (value "147")
      (footprint "eagle-import:.0603-C-NOSILK")
      (fields (field (name "MFR") "Panasonic") (field (name "MPN") "ERJ-3EKF1470V"))
      (libsource (lib "eagle-import") (part "R-US_0603-C-NOSILK"))
    )
    (comp (ref "R3")
      (value "17.8")
      (footprint "eagle-import:.0603-C-NOSILK")
      (fields (field (name "MFR") "Panasonic") (field (name "MPN") "ERJ-3EKF17R8V"))
      (libsource (lib "eagle-import") (part "R-US_0603-C-NOSILK"))
    )
    (comp (ref "R4")
      (value "294")
      (footprint "eagle-import:.0603-C-NOSILK")
      (fields (field (name "MFR") "Panasonic") (field (name "MPN") "ERJ-3EKF2940V"))
      (libsource (lib "eagle-import") (part "R-US_0603-C-NOSILK"))
    )
    (comp (ref "R17")
      (value "0")
      (footprint "eagle-import:R0805")
      (fields (field (name "MFR") "Panasonic") (field (name "MPN") "ERJ-6GEY0R00V"))
      (libsource (lib "eagle-import") (part "rcl_334_R-US_R0805"))
    )
    (comp (ref "R18")
      (value "1.2")
      (footprint "eagle-import:R0402")
      (fields (field (name "MFR") "Panasonic") (field (name "MPN") "ERJ-2GEJ1R2X"))
      (libsource (lib "eagle-import") (part "rcl_334_R-US_R0402"))
    )
    (comp (ref "R19")
      (value "110")
      (footprint "eagle-import:.0402-B-NOSILK")
      (fields (field (name "MFR") "Panasonic") (field (name "MPN") "ERJ-2RKF1100X"))
      (libsource (lib "eagle-import") (part "R-US_0402-B-NOSILK"))
    )
    (comp (ref "R20")
      (value "220")
      (footprint "eagle-import:.0603-C-NOSILK")
      (fields (field (name "MFR") "Panasonic") (field (name "MPN") "ERJ-3EKF2200V"))
      (libsource (lib "eagle-import") (part "R-US_0603-C-NOSILK"))
    )
    (comp (ref "U10")
      (value "TQP9111")
      (footprint "eagle-import:QFN50P400X400X102-21N")
      (fields (field (name "MFR") "Qorvo"))
      (libsource (lib "eagle-import") (part "TQP9111"))
    )
    (comp (ref "C30")
      (value "100p")
      (footprint "eagle-import:.0402-B-NOSILK")
      (fields (field (name "MFR") "Murata") (field (name "MPN") "GCM1555C1H101JA16D "))
      (libsource (lib "eagle-import") (part "C-EU0402-B-NOSILK"))
    )
    (comp (ref "C31")
      (value "100n")
      (footprint "eagle-import:.0402-B-NOSILK")
      (fields (field (name "MFR") "TDK Corporation") (field (name "MPN") "CGA2B1X7R1C104K050BC"))
      (libsource (lib "eagle-import") (part "C-EU0402-B-NOSILK"))
    )
    (comp (ref "C32")
      (value "DNP")
      (footprint "eagle-import:.0402-B-NOSILK")
      (libsource (lib "eagle-import") (part "C-EU0402-B-NOSILK"))
    )
    (comp (ref "C33")
      (value "100p")
      (footprint "eagle-import:.0402-B-NOSILK")
      (fields (field (name "MFR") "Murata") (field (name "MPN") "GCM1555C1H101JA16D "))
      (libsource (lib "eagle-import") (part "C-EU0402-B-NOSILK"))
    )
    (comp (ref "R24")
      (value "10k")
      (footprint "eagle-import:.0402-B-NOSILK")
      (fields (field (name "MFR") "Panasonic") (field (name "MPN") "ERJ-2RKF1002X"))
      (libsource (lib "eagle-import") (part "R-US_0402-B-NOSILK"))
    )
    (comp (ref "R25")
      (value "5.62k")
      (footprint "eagle-import:.0402-B-NOSILK")
      (fields (field (name "MFR") "Panasonic") (field (name "MPN") "ERJ-2RKF5621X"))
      (libsource (lib "eagle-import") (part "R-US_0402-B-NOSILK"))
    )
    (comp (ref "R26")
      (value "10k")
      (footprint "eagle-import:.0402-B-NOSILK")
      (fields (field (name "MFR") "Panasonic") (field (name "MPN") "ERJ-2RKF1002X"))
      (libsource (lib "eagle-import") (part "R-US_0402-B-NOSILK"))
    )
    (comp (ref "R27")
      (value "5.62k")
      (footprint "eagle-import:.0402-B-NOSILK")
      (fields (field (name "MFR") "Panasonic") (field (name "MPN") "ERJ-2RKF5621X"))
      (libsource (lib "eagle-import") (part "R-US_0402-B-NOSILK"))
    )
    (comp (ref "U8")
      (value "QPC1022")
      (footprint "eagle-import:QPC1022")
      (fields (field (name "MFR") "Qorvo"))
      (libsource (lib "eagle-import") (part "QPC1022"))
    )
    (comp (ref "C1")
      (value "15p")
      (footprint "eagle-import:.0402-C-NOSILK")
      (fields (field (name "MFR") "Murata") (field (name "MPN") "GJM1555C1H150JB01D "))
      (libsource (lib "eagle-import") (part "C-EU0402-C-NOSILK"))
    )
    (comp (ref "C2")
      (value "15p")
      (footprint "eagle-import:.0402-B-NOSILK")
      (fields (field (name "MFR") "Murata") (field (name "MPN") "GJM1555C1H150JB01D "))
      (libsource (lib "eagle-import") (part "C-EU0402-B-NOSILK"))
    )
    (comp (ref "C3")
      (value "15p")
      (footprint "eagle-import:.0402-C-NOSILK")
      (fields (field (name "MFR") "Murata") (field (name "MPN") "GJM1555C1H150JB01D "))
      (libsource (lib "eagle-import") (part "C-EU0402-C-NOSILK"))
    )
    (comp (ref "C4")
      (value "1uF")
      (footprint "eagle-import:.0603-B-NOSILK")
      (fields (field (name "MFR") "KEMET") (field (name "MPN") "C0603X105M4RACAUTO "))
      (libsource (lib "eagle-import") (part "C-EU0603-B-NOSILK"))
    )
    (comp (ref "C5")
      (value "100n")
      (footprint "eagle-import:.0402-B-NOSILK")
      (fields (field (name "MFR") "TDK Corporation") (field (name "MPN") "CGA2B1X7R1C104K050BC"))
      (libsource (lib "eagle-import") (part "C-EU0402-B-NOSILK"))
    )
    (comp (ref "C7")
      (value "100n")
      (footprint "eagle-import:.0402-B-NOSILK")
      (fields (field (name "MFR") "TDK") (field (name "MPN") "CGA2B1X7R1C104K050BC"))
      (libsource (lib "eagle-import") (part "C-EU0402-B-NOSILK"))
    )
    (comp (ref "C26")
      (value "15p")
      (footprint "eagle-import:.0402-C-NOSILK")
      (fields (field (name "MFR") "Murata") (field (name "MPN") "GJM1555C1H150JB01D "))
      (libsource (lib "eagle-import") (part "C-EU0402-C-NOSILK"))
    )
    (comp (ref "C27")
      (value "15p")
      (footprint "eagle-import:.0402-B-NOSILK")
      (fields (field (name "MFR") "Murata") (field (name "MPN") "GJM1555C1H150JB01D "))
      (libsource (lib "eagle-import") (part "C-EU0402-B-NOSILK"))
    )
    (comp (ref "C28")
      (value "15p")
      (footprint "eagle-import:.0402-C-NOSILK")
      (fields (field (name "MFR") "Murata") (field (name "MPN") "GJM1555C1H150JB01D "))
      (libsource (lib "eagle-import") (part "C-EU0402-C-NOSILK"))
    )
    (comp (ref "C29")
      (value "1uF")
      (footprint "eagle-import:.0603-B-NOSILK")
      (fields (field (name "MFR") "KEMET") (field (name "MPN") "C0603X105M4RACAUTO "))
      (libsource (lib "eagle-import") (part "C-EU0603-B-NOSILK"))
    )
    (comp (ref "FL1")
      (value "QPQ1907")
      (footprint "eagle-import:FIL_B39162B9417K610")
      (fields (field (name "MFR") "Qorvo") (field (name "MPN") "885071-A") (field (name "MPN_1") "QPQ1907"))
      (libsource (lib "eagle-import") (part "QPQ1907"))
    )
    (comp (ref "FL2")
      (value "QPQ1907")
      (footprint "eagle-import:FIL_B39162B9417K610")
      (fields (field (name "MFR") "Qorvo") (field (name "MPN") "885071-A") (field (name "MPN_1") "QPQ1907"))
      (libsource (lib "eagle-import") (part "QPQ1907"))
    )
    (comp (ref "J4")
      (value "142-0701-851_ALT")
      (footprint "eagle-import:142-0701-851")
      (fields (field (name "MFR") "Cinch") (field (name "MPN") "142-0701-851"))
      (libsource (lib "eagle-import") (part "142-0701-851_ALT"))
    )
    (comp (ref "JP4")
      (value "PINHD-1X3")
      (footprint "eagle-import:1X03")
      (fields (field (name "MFR") "Molex") (field (name "MPN") "22-23-2031"))
      (libsource (lib "eagle-import") (part "PINHD-1X3"))
    )
    (comp (ref "L4")
      (value "68nH")
      (footprint "eagle-import:0603CS-68NXJLW")
      (fields
        (field (name "MFR") "COILCRAFT")
        (field (name "MPN") "0603CS-68NXJLW")
        (field (name "MPN_1") "0603CS-18NXJLW")
      )
      (libsource (lib "eagle-import") (part "0603CS-68NXJLW"))
    )
    (comp (ref "L5")
      (value "68nH")
      (footprint "eagle-import:0603CS-68NXJLW")
      (fields
        (field (name "MFR") "COILCRAFT")
        (field (name "MPN") "0603CS-68NXJLW")
        (field (name "MPN_1") "0603CS-18NXJLW")
      )
      (libsource (lib "eagle-import") (part "0603CS-68NXJLW"))
    )
    (comp (ref "R6")
      (value "17.8")
      (footprint "eagle-import:.0402-C-NOSILK")
      (fields (field (name "MFR") "Panasonic") (field (name "MPN") "ERJ-2RKF17R8X"))
      (libsource (lib "eagle-import") (part "R-US_0402-C-NOSILK"))
    )
    (comp (ref "R7")
      (value "294")
      (footprint "eagle-import:.0402-C-NOSILK")
      (fields (field (name "MFR") "Panasonic") (field (name "MPN") "ERJ-2RKF2940X"))
      (libsource (lib "eagle-import") (part "R-US_0402-C-NOSILK"))
    )
    (comp (ref "R8")
      (value "294")
      (footprint "eagle-import:.0402-C-NOSILK")
      (fields (field (name "MFR") "Panasonic") (field (name "MPN") "ERJ-2RKF2940X"))
      (libsource (lib "eagle-import") (part "R-US_0402-C-NOSILK"))
    )
    (comp (ref "R9")
      (value "17.8")
      (footprint "eagle-import:.0402-C-NOSILK")
      (fields (field (name "MFR") "Panasonic") (field (name "MPN") "ERJ-2RKF17R8X"))
      (libsource (lib "eagle-import") (part "R-US_0402-C-NOSILK"))
    )
    (comp (ref "R10")
      (value "294")
      (footprint "eagle-import:.0402-C-NOSILK")
      (fields (field (name "MFR") "Panasonic") (field (name "MPN") "ERJ-2RKF2940X"))
      (libsource (lib "eagle-import") (part "R-US_0402-C-NOSILK"))
    )
    (comp (ref "R13")
      (value "294")
      (footprint "eagle-import:.0402-C-NOSILK")
      (fields (field (name "MFR") "Panasonic") (field (name "MPN") "ERJ-2RKF2940X"))
      (libsource (lib "eagle-import") (part "R-US_0402-C-NOSILK"))
    )
    (comp (ref "R14")
      (value "0")
      (footprint "eagle-import:.0603-B-NOSILK")
      (fields (field (name "MFR") "Panasonic") (field (name "MPN") "ERJ-3GEY0R00V"))
      (libsource (lib "eagle-import") (part "R-US_0603-B-NOSILK"))
    )
    (comp (ref "R23")
      (value "0")
      (footprint "eagle-import:.0603-B-NOSILK")
      (fields (field (name "MFR") "Panasonic") (field (name "MPN") "ERJ-3GEY0R00V"))
      (libsource (lib "eagle-import") (part "R-US_0603-B-NOSILK"))
    )
    (comp (ref "R29")
      (value "10k")
      (footprint "eagle-import:.0402-B-NOSILK")
      (fields (field (name "MFR") "Panasonic") (field (name "MPN") "ERJ-2GEJ103X"))
      (libsource (lib "eagle-import") (part "R-US_0402-B-NOSILK"))
    )
    (comp (ref "R30")
      (value "33k")
      (footprint "eagle-import:.0402-B-NOSILK")
      (fields (field (name "MFR") "Panasonic") (field (name "MPN") "ERJ-2RKF2940X"))
      (libsource (lib "eagle-import") (part "R-US_0402-B-NOSILK"))
    )
    (comp (ref "R31")
      (value "10k")
      (footprint "eagle-import:.0402-B-NOSILK")
      (fields (field (name "MFR") "Panasonic") (field (name "MPN") "ERJ-2RKF2940X"))
      (libsource (lib "eagle-import") (part "R-US_0402-B-NOSILK"))
    )
    (comp (ref "U4")
      (value "TQP3M903X")
      (footprint "eagle-import:DFN8-2X2-WITH-PAD")
      (fields (field (name "MFR") "Qorvo") (field (name "MPN") "TQP3M9037 "))
      (libsource (lib "eagle-import") (part "TQP3M903X"))
    )
    (comp (ref "U5")
      (value "TQP3M903X")
      (footprint "eagle-import:DFN8-2X2-WITH-PAD")
      (fields (field (name "MFR") "Qorvo") (field (name "MPN") "TQP3M9037 "))
      (libsource (lib "eagle-import") (part "TQP3M903X"))
    )
    (comp (ref "U6")
      (value "SN74LV1T34DBVR")
      (footprint "eagle-import:SOT95P280X145-5N")
      (fields (field (name "MFR") "Texas Instruments"))
      (libsource (lib "eagle-import") (part "SN74LV1T34DBVR"))
    )
    (comp (ref "U12")
      (value "SN74LVC1G32DBVR")
      (footprint "eagle-import:DBV5")
      (fields (field (name "MFR") "Texas Instruments"))
      (libsource (lib "eagle-import") (part "SN74LVC1G32DBVR"))
    )
    (comp (ref "C34")
      (value "4.7uF")
      (footprint "eagle-import:C1206")
      (fields
        (field (name "MFR") "Murata")
        (field (name "MPN") "GCJ31CR71C475KA01L")
        (field (name "VOLTAGE") "16V")
      )
      (libsource (lib "eagle-import") (part "rcl_334_C-EUC1206"))
    )
    (comp (ref "C35")
      (value "22uF")
      (footprint "eagle-import:C1210")
      (fields (field (name "MFR") "Murata") (field (name "MPN") "GCJ32ER71C226KE01L"))
      (libsource (lib "eagle-import") (part "rcl_334_C-EUC1210"))
    )
    (comp (ref "JP6")
      (value "PINHD-1X4")
      (footprint "eagle-import:1X04")
      (libsource (lib "eagle-import") (part "PINHD-1X4"))
    )
  )
  (nets
    (net (code "1") (name "+5V") (class "Default")
      (node (ref "C10") (pin "1") (pinfunction "1_1") (pintype "passive"))
      (node (ref "C14") (pin "1") (pinfunction "1_1") (pintype "passive"))
      (node (ref "C30") (pin "1") (pinfunction "1_1") (pintype "passive"))
      (node (ref "C31") (pin "1") (pinfunction "1_1") (pintype "passive"))
      (node (ref "C34") (pin "1") (pinfunction "1_1") (pintype "passive"))
      (node (ref "C35") (pin "1") (pinfunction "1_1") (pintype "passive"))
      (node (ref "C39") (pin "1") (pinfunction "1_1") (pintype "passive"))
      (node (ref "C41") (pin "1") (pinfunction "1_1") (pintype "passive"))
      (node (ref "C5") (pin "1") (pinfunction "1_1") (pintype "passive"))
      (node (ref "C6") (pin "1") (pinfunction "1_1") (pintype "passive"))
      (node (ref "C7") (pin "1") (pinfunction "1_1") (pintype "passive"))
      (node (ref "C8") (pin "1") (pinfunction "1_1") (pintype "passive"))
      (node (ref "C9") (pin "1") (pinfunction "1_1") (pintype "passive"))
      (node (ref "JP6") (pin "1") (pinfunction "1_1") (pintype "passive"))
      (node (ref "JP6") (pin "2") (pinfunction "2_2") (pintype "passive"))
      (node (ref "LED2") (pin "2") (pinfunction "A_2") (pintype "bidirectional"))
      (node (ref "R14") (pin "2") (pinfunction "2_2") (pintype "passive"))
      (node (ref "R15") (pin "1") (pinfunction "1_1") (pintype "passive"))
      (node (ref "R17") (pin "2") (pinfunction "2_2") (pintype "passive"))
      (node (ref "R23") (pin "2") (pinfunction "2_2") (pintype "passive"))
      (node (ref "R24") (pin "1") (pinfunction "1_1") (pintype "passive"))
      (node (ref "R5") (pin "2") (pinfunction "2_2") (pintype "passive"))
      (node (ref "U1") (pin "5") (pinfunction "VCC_5") (pintype "power_in"))
      (node (ref "U11") (pin "5") (pinfunction "VCC_5") (pintype "bidirectional"))
      (node (ref "U12") (pin "5") (pinfunction "VCC_5") (pintype "power_in"))
      (node (ref "U2") (pin "5") (pinfunction "V+_5") (pintype "power_in"))
      (node (ref "U3") (pin "4") (pinfunction "DIV_4") (pintype "input"))
      (node (ref "U3") (pin "5") (pinfunction "V+_5") (pintype "power_in"))
      (node (ref "U6") (pin "5") (pinfunction "VCC_5") (pintype "bidirectional"))
      (node (ref "U7") (pin "7") (pinfunction "VDD_7") (pintype "power_in"))
      (node (ref "U8") (pin "7") (pinfunction "VDD_7") (pintype "power_in"))
      (node (ref "U9") (pin "5") (pinfunction "VCC_5") (pintype "bidirectional"))
    )
    (net (code "2") (name "ANT_SEL+3.3V") (class "Default")
      (node (ref "JP3") (pin "1") (pinfunction "1_1") (pintype "passive"))
      (node (ref "JP3") (pin "3") (pinfunction "3_3") (pintype "passive"))
      (node (ref "R28") (pin "2") (pinfunction "2_2") (pintype "passive"))
      (node (ref "U9") (pin "2") (pinfunction "A_2") (pintype "bidirectional"))
    )
    (net (code "3") (name "ANT_SEL_+5.0V") (class "Default")
      (node (ref "R21") (pin "1") (pinfunction "1_1") (pintype "passive"))
      (node (ref "U9") (pin "4") (pinfunction "Y_4") (pintype "bidirectional"))
    )
    (net (code "4") (name "AR9271_TX_+3.3V") (class "Default")
      (node (ref "JP1") (pin "1") (pinfunction "1_1") (pintype "passive"))
      (node (ref "JP1") (pin "3") (pinfunction "3_3") (pintype "passive"))
      (node (ref "R37") (pin "2") (pinfunction "2_2") (pintype "passive"))
      (node (ref "U11") (pin "2") (pinfunction "A_2") (pintype "bidirectional"))
    )
    (net (code "5") (name "GND") (class "Default")
      (node (ref "C10") (pin "2") (pinfunction "2_2") (pintype "passive"))
      (node (ref "C11") (pin "2") (pinfunction "2_2") (pintype "passive"))
      (node (ref "C12") (pin "2") (pinfunction "2_2") (pintype "passive"))
      (node (ref "C14") (pin "2") (pinfunction "2_2") (pintype "passive"))
      (node (ref "C15") (pin "2") (pinfunction "2_2") (pintype "passive"))
      (node (ref "C16") (pin "2") (pinfunction "2_2") (pintype "passive"))
      (node (ref "C17") (pin "2") (pinfunction "2_2") (pintype "passive"))
      (node (ref "C18") (pin "2") (pinfunction "2_2") (pintype "passive"))
      (node (ref "C19") (pin "2") (pinfunction "2_2") (pintype "passive"))
      (node (ref "C2") (pin "1") (pinfunction "1_1") (pintype "passive"))
      (node (ref "C21") (pin "2") (pinfunction "2_2") (pintype "passive"))
      (node (ref "C22") (pin "2") (pinfunction "2_2") (pintype "passive"))
      (node (ref "C23") (pin "2") (pinfunction "2_2") (pintype "passive"))
      (node (ref "C27") (pin "1") (pinfunction "1_1") (pintype "passive"))
      (node (ref "C29") (pin "2") (pinfunction "2_2") (pintype "passive"))
      (node (ref "C30") (pin "2") (pinfunction "2_2") (pintype "passive"))
      (node (ref "C31") (pin "2") (pinfunction "2_2") (pintype "passive"))
      (node (ref "C32") (pin "2") (pinfunction "2_2") (pintype "passive"))
      (node (ref "C33") (pin "2") (pinfunction "2_2") (pintype "passive"))
      (node (ref "C34") (pin "2") (pinfunction "2_2") (pintype "passive"))
      (node (ref "C35") (pin "2") (pinfunction "2_2") (pintype "passive"))
      (node (ref "C39") (pin "2") (pinfunction "2_2") (pintype "passive"))
      (node (ref "C4") (pin "2") (pinfunction "2_2") (pintype "passive"))
      (node (ref "C41") (pin "2") (pinfunction "2_2") (pintype "passive"))
      (node (ref "C5") (pin "2") (pinfunction "2_2") (pintype "passive"))
      (node (ref "C6") (pin "2") (pinfunction "2_2") (pintype "passive"))
      (node (ref "C7") (pin "2") (pinfunction "2_2") (pintype "passive"))
      (node (ref "C8") (pin "2") (pinfunction "2_2") (pintype "passive"))
      (node (ref "C9") (pin "2") (pinfunction "2_2") (pintype "passive"))
      (node (ref "FL1") (pin "2") (pinfunction "GND_2") (pintype "power_in"))
      (node (ref "FL1") (pin "3") (pinfunction "GND_3") (pintype "power_in"))
      (node (ref "FL1") (pin "5") (pinfunction "GND_5") (pintype "power_in"))
      (node (ref "FL2") (pin "2") (pinfunction "GND_2") (pintype "power_in"))
      (node (ref "FL2") (pin "3") (pinfunction "GND_3") (pintype "power_in"))
      (node (ref "FL2") (pin "5") (pinfunction "GND_5") (pintype "power_in"))
      (node (ref "J1") (pin "GND1") (pinfunction "GND_GND1") (pintype "bidirectional"))
      (node (ref "J1") (pin "GND2") (pinfunction "GND_GND2") (pintype "bidirectional"))
      (node (ref "J1") (pin "GND3") (pinfunction "GND_GND3") (pintype "bidirectional"))
      (node (ref "J1") (pin "GND4") (pinfunction "GND_GND4") (pintype "bidirectional"))
      (node (ref "J2") (pin "GND1") (pinfunction "GND_GND1") (pintype "bidirectional"))
      (node (ref "J2") (pin "GND2") (pinfunction "GND_GND2") (pintype "bidirectional"))
      (node (ref "J2") (pin "GND3") (pinfunction "GND_GND3") (pintype "bidirectional"))
      (node (ref "J2") (pin "GND4") (pinfunction "GND_GND4") (pintype "bidirectional"))
      (node (ref "J3") (pin "GND1") (pinfunction "GND_GND1") (pintype "bidirectional"))
      (node (ref "J3") (pin "GND2") (pinfunction "GND_GND2") (pintype "bidirectional"))
      (node (ref "J3") (pin "GND3") (pinfunction "GND_GND3") (pintype "bidirectional"))
      (node (ref "J3") (pin "GND4") (pinfunction "GND_GND4") (pintype "bidirectional"))
      (node (ref "J4") (pin "GND1") (pinfunction "GND_GND1") (pintype "bidirectional"))
      (node (ref "J4") (pin "GND2") (pinfunction "GND_GND2") (pintype "bidirectional"))
      (node (ref "J4") (pin "GND3") (pinfunction "GND_GND3") (pintype "bidirectional"))
      (node (ref "J4") (pin "GND4") (pinfunction "GND_GND4") (pintype "bidirectional"))
      (node (ref "J6") (pin "GND1") (pinfunction "GND_GND1") (pintype "bidirectional"))
      (node (ref "J6") (pin "GND2") (pinfunction "GND_GND2") (pintype "bidirectional"))
      (node (ref "J6") (pin "GND3") (pinfunction "GND_GND3") (pintype "bidirectional"))
      (node (ref "J6") (pin "GND4") (pinfunction "GND_GND4") (pintype "bidirectional"))
      (node (ref "J7") (pin "GND1") (pinfunction "GND_GND1") (pintype "bidirectional"))
      (node (ref "J7") (pin "GND2") (pinfunction "GND_GND2") (pintype "bidirectional"))
      (node (ref "J7") (pin "GND3") (pinfunction "GND_GND3") (pintype "bidirectional"))
      (node (ref "J7") (pin "GND4") (pinfunction "GND_GND4") (pintype "bidirectional"))
      (node (ref "JP1") (pin "2") (pinfunction "2_2") (pintype "passive"))
      (node (ref "JP3") (pin "2") (pinfunction "2_2") (pintype "passive"))
      (node (ref "JP4") (pin "2") (pinfunction "2_2") (pintype "passive"))
      (node (ref "JP6") (pin "3") (pinfunction "3_3") (pintype "passive"))
      (node (ref "JP6") (pin "4") (pinfunction "4_4") (pintype "passive"))
      (node (ref "R10") (pin "2") (pinfunction "2_2") (pintype "passive"))
      (node (ref "R11") (pin "1") (pinfunction "1_1") (pintype "passive"))
      (node (ref "R12") (pin "1") (pinfunction "1_1") (pintype "passive"))
      (node (ref "R13") (pin "2") (pinfunction "2_2") (pintype "passive"))
      (node (ref "R16") (pin "2") (pinfunction "2_2") (pintype "passive"))
      (node (ref "R2") (pin "1") (pinfunction "1_1") (pintype "passive"))
      (node (ref "R22") (pin "2") (pinfunction "2_2") (pintype "passive"))
      (node (ref "R25") (pin "2") (pinfunction "2_2") (pintype "passive"))
      (node (ref "R27") (pin "2") (pinfunction "2_2") (pintype "passive"))
      (node (ref "R28") (pin "1") (pinfunction "1_1") (pintype "passive"))
      (node (ref "R29") (pin "1") (pinfunction "1_1") (pintype "passive"))
      (node (ref "R31") (pin "2") (pinfunction "2_2") (pintype "passive"))
      (node (ref "R32") (pin "1") (pinfunction "1_1") (pintype "passive"))
      (node (ref "R36") (pin "1") (pinfunction "1_1") (pintype "passive"))
      (node (ref "R37") (pin "1") (pinfunction "1_1") (pintype "passive"))
      (node (ref "R4") (pin "2") (pinfunction "2_2") (pintype "passive"))
      (node (ref "R7") (pin "2") (pinfunction "2_2") (pintype "passive"))
      (node (ref "R8") (pin "2") (pinfunction "2_2") (pintype "passive"))
      (node (ref "SW1") (pin "1") (pinfunction "O_1") (pintype "passive"))
      (node (ref "U1") (pin "3") (pinfunction "GND_3") (pintype "power_in"))
      (node (ref "U10") (pin "1") (pinfunction "GND_1") (pintype "power_in"))
      (node (ref "U10") (pin "10") (pinfunction "GND_10") (pintype "power_in"))
      (node (ref "U10") (pin "11") (pinfunction "GND_11") (pintype "power_in"))
      (node (ref "U10") (pin "15") (pinfunction "GND_15") (pintype "power_in"))
      (node (ref "U10") (pin "17") (pinfunction "GND_17") (pintype "power_in"))
      (node (ref "U10") (pin "19") (pinfunction "GND_19") (pintype "power_in"))
      (node (ref "U10") (pin "21") (pinfunction "GND_21") (pintype "power_in"))
      (node (ref "U10") (pin "5") (pinfunction "GND_5") (pintype "power_in"))
      (node (ref "U10") (pin "7") (pinfunction "GND_7") (pintype "power_in"))
      (node (ref "U10") (pin "9") (pinfunction "GND_9") (pintype "power_in"))
      (node (ref "U11") (pin "3") (pinfunction "GND_3") (pintype "bidirectional"))
      (node (ref "U12") (pin "3") (pinfunction "GND_3") (pintype "power_in"))
      (node (ref "U2") (pin "2") (pinfunction "GND_2") (pintype "power_in"))
      (node (ref "U2") (pin "4") (pinfunction "DIV_4") (pintype "input"))
      (node (ref "U3") (pin "2") (pinfunction "GND_2") (pintype "power_in"))
      (node (ref "U4") (pin "1") (pinfunction "GND_1") (pintype "power_in"))
      (node (ref "U4") (pin "3") (pinfunction "GND_3") (pintype "power_in"))
      (node (ref "U4") (pin "4") (pinfunction "GND_4") (pintype "power_in"))
      (node (ref "U4") (pin "5") (pinfunction "GND_5") (pintype "power_in"))
      (node (ref "U4") (pin "8") (pinfunction "GND_8") (pintype "power_in"))
      (node (ref "U4") (pin "PAD") (pinfunction "GND_PAD") (pintype "power_in"))
      (node (ref "U5") (pin "1") (pinfunction "GND_1") (pintype "power_in"))
      (node (ref "U5") (pin "3") (pinfunction "GND_3") (pintype "power_in"))
      (node (ref "U5") (pin "4") (pinfunction "GND_4") (pintype "power_in"))
      (node (ref "U5") (pin "5") (pinfunction "GND_5") (pintype "power_in"))
      (node (ref "U5") (pin "8") (pinfunction "GND_8") (pintype "power_in"))
      (node (ref "U5") (pin "PAD") (pinfunction "GND_PAD") (pintype "power_in"))
      (node (ref "U6") (pin "3") (pinfunction "GND_3") (pintype "bidirectional"))
      (node (ref "U7") (pin "1") (pinfunction "GND_1") (pintype "power_in"))
      (node (ref "U7") (pin "3") (pinfunction "GND_3") (pintype "power_in"))
      (node (ref "U7") (pin "9") (pinfunction "GND_9") (pintype "power_in"))
      (node (ref "U8") (pin "1") (pinfunction "GND_1") (pintype "power_in"))
      (node (ref "U8") (pin "3") (pinfunction "GND_3") (pintype "power_in"))
      (node (ref "U8") (pin "9") (pinfunction "GND_9") (pintype "power_in"))
      (node (ref "U9") (pin "3") (pinfunction "GND_3") (pintype "bidirectional"))
    )
    (net (code "6") (name "LNA_DISABLE+3.3V") (class "Default")
      (node (ref "JP4") (pin "1") (pinfunction "1_1") (pintype "passive"))
      (node (ref "JP4") (pin "3") (pinfunction "3_3") (pintype "passive"))
      (node (ref "R29") (pin "2") (pinfunction "2_2") (pintype "passive"))
      (node (ref "U6") (pin "2") (pinfunction "A_2") (pintype "bidirectional"))
    )
    (net (code "7") (name "LNA_DISABLE_+5.0V") (class "Default")
      (node (ref "U12") (pin "2") (pinfunction "B_2") (pintype "input"))
      (node (ref "U6") (pin "4") (pinfunction "Y_4") (pintype "bidirectional"))
    )
    (net (code "8") (name "N$17") (class "Default")
      (node (ref "R30") (pin "2") (pinfunction "2_2") (pintype "passive"))
      (node (ref "U12") (pin "4") (pinfunction "Y_4") (pintype "output"))
    )
    (net (code "9") (name "Net-(C1-Pad1)") (class "Default")
      (node (ref "C1") (pin "1") (pinfunction "1_1") (pintype "passive"))
      (node (ref "R10") (pin "1") (pinfunction "1_1") (pintype "passive"))
      (node (ref "R9") (pin "2") (pinfunction "2_2") (pintype "passive"))
    )
    (net (code "10") (name "Net-(C2-Pad2)") (class "Default")
      (node (ref "C2") (pin "2") (pinfunction "2_2") (pintype "passive"))
      (node (ref "C4") (pin "1") (pinfunction "1_1") (pintype "passive"))
      (node (ref "L5") (pin "2") (pinfunction "2_2") (pintype "bidirectional"))
      (node (ref "R14") (pin "1") (pinfunction "1_1") (pintype "passive"))
    )
    (net (code "11") (name "Net-(C15-Pad1)") (class "Default")
      (node (ref "C15") (pin "1") (pinfunction "1_1") (pintype "passive"))
      (node (ref "C16") (pin "1") (pinfunction "1_1") (pintype "passive"))
      (node (ref "C17") (pin "1") (pinfunction "1_1") (pintype "passive"))
      (node (ref "C19") (pin "1") (pinfunction "1_1") (pintype "passive"))
      (node (ref "L1") (pin "2") (pinfunction "2_2") (pintype "bidirectional"))
      (node (ref "L2") (pin "2") (pinfunction "2_2") (pintype "bidirectional"))
      (node (ref "R17") (pin "1") (pinfunction "1_1") (pintype "passive"))
      (node (ref "R20") (pin "2") (pinfunction "2_2") (pintype "passive"))
    )
    (net (code "12") (name "Net-(C20-Pad1)") (class "Default")
      (node (ref "C20") (pin "1") (pinfunction "1_1") (pintype "passive"))
      (node (ref "C23") (pin "1") (pinfunction "1_1") (pintype "passive"))
      (node (ref "L3") (pin "2") (pinfunction "2_2") (pintype "bidirectional"))
    )
    (net (code "13") (name "Net-(C21-Pad1)") (class "Default")
      (node (ref "C21") (pin "1") (pinfunction "1_1") (pintype "passive"))
      (node (ref "L3") (pin "1") (pinfunction "1_1") (pintype "bidirectional"))
      (node (ref "U10") (pin "12") (pinfunction "RFOUT_12") (pintype "output"))
      (node (ref "U10") (pin "13") (pinfunction "RFOUT_13") (pintype "output"))
      (node (ref "U10") (pin "14") (pinfunction "RFOUT_14") (pintype "output"))
    )
    (net (code "14") (name "Net-(C22-Pad1)") (class "Default")
      (node (ref "C22") (pin "1") (pinfunction "1_1") (pintype "passive"))
      (node (ref "C24") (pin "2") (pinfunction "2_2") (pintype "passive"))
      (node (ref "R18") (pin "1") (pinfunction "1_1") (pintype "passive"))
    )
    (net (code "15") (name "Net-(C24-Pad1)") (class "Default")
      (node (ref "C24") (pin "1") (pinfunction "1_1") (pintype "passive"))
      (node (ref "R3") (pin "2") (pinfunction "2_2") (pintype "passive"))
      (node (ref "R4") (pin "1") (pinfunction "1_1") (pintype "passive"))
    )
    (net (code "16") (name "Net-(C27-Pad2)") (class "Default")
      (node (ref "C27") (pin "2") (pinfunction "2_2") (pintype "passive"))
      (node (ref "C29") (pin "1") (pinfunction "1_1") (pintype "passive"))
      (node (ref "L4") (pin "2") (pinfunction "2_2") (pintype "bidirectional"))
      (node (ref "R23") (pin "1") (pinfunction "1_1") (pintype "passive"))
    )
    (net (code "17") (name "Net-(C28-Pad2)") (class "Default")
      (node (ref "C28") (pin "2") (pinfunction "2_2") (pintype "passive"))
      (node (ref "R6") (pin "1") (pinfunction "1_1") (pintype "passive"))
      (node (ref "R8") (pin "1") (pinfunction "1_1") (pintype "passive"))
    )
    (net (code "18") (name "Net-(FL1-OUT)") (class "Default")
      (node (ref "C26") (pin "1") (pinfunction "1_1") (pintype "passive"))
      (node (ref "FL1") (pin "4") (pinfunction "OUT_4") (pintype "passive"))
    )
    (net (code "19") (name "Net-(FL2-IN)") (class "Default")
      (node (ref "FL2") (pin "1") (pinfunction "IN_1") (pintype "passive"))
      (node (ref "R6") (pin "2") (pinfunction "2_2") (pintype "passive"))
      (node (ref "R7") (pin "1") (pinfunction "1_1") (pintype "passive"))
    )
    (net (code "20") (name "Net-(FL2-OUT)") (class "Default")
      (node (ref "FL2") (pin "4") (pinfunction "OUT_4") (pintype "passive"))
      (node (ref "R13") (pin "1") (pinfunction "1_1") (pintype "passive"))
      (node (ref "R9") (pin "1") (pinfunction "1_1") (pintype "passive"))
    )
    (net (code "21") (name "Net-(J1-CTR)") (class "Default")
      (node (ref "J1") (pin "RF1") (pinfunction "CTR_RF1") (pintype "bidirectional"))
      (node (ref "R1") (pin "2") (pinfunction "2_2") (pintype "passive"))
      (node (ref "R3") (pin "1") (pinfunction "1_1") (pintype "passive"))
    )
    (net (code "22") (name "Net-(J2-CTR)") (class "Default")
      (node (ref "J2") (pin "RF1") (pinfunction "CTR_RF1") (pintype "bidirectional"))
      (node (ref "U7") (pin "8") (pinfunction "RF2_8") (pintype "bidirectional"))
    )
    (net (code "23") (name "Net-(J3-CTR)") (class "Default")
      (node (ref "J3") (pin "RF1") (pinfunction "CTR_RF1") (pintype "bidirectional"))
      (node (ref "U7") (pin "4") (pinfunction "RF1_4") (pintype "bidirectional"))
    )
    (net (code "24") (name "Net-(J4-CTR)") (class "Default")
      (node (ref "C3") (pin "2") (pinfunction "2_2") (pintype "passive"))
      (node (ref "J4") (pin "RF1") (pinfunction "CTR_RF1") (pintype "bidirectional"))
    )
    (net (code "25") (name "Net-(J6-CTR)") (class "Default")
      (node (ref "J6") (pin "RF1") (pinfunction "CTR_RF1") (pintype "bidirectional"))
      (node (ref "J7") (pin "RF1") (pinfunction "CTR_RF1") (pintype "bidirectional"))
    )
    (net (code "26") (name "Net-(LED1-A)") (class "Default")
      (node (ref "LED1") (pin "2") (pinfunction "A_2") (pintype "bidirectional"))
      (node (ref "U1") (pin "4") (pinfunction "Y_4") (pintype "output"))
      (node (ref "U2") (pin "1") (pinfunction "IN_1") (pintype "input"))
      (node (ref "U3") (pin "1") (pinfunction "IN_1") (pintype "input"))
    )
    (net (code "27") (name "Net-(LED1-K)") (class "Default")
      (node (ref "LED1") (pin "1") (pinfunction "K_1") (pintype "bidirectional"))
      (node (ref "R32") (pin "2") (pinfunction "2_2") (pintype "passive"))
    )
    (net (code "28") (name "Net-(LED2-K)") (class "Default")
      (node (ref "LED2") (pin "1") (pinfunction "K_1") (pintype "bidirectional"))
      (node (ref "R36") (pin "2") (pinfunction "2_2") (pintype "passive"))
    )
    (net (code "29") (name "Net-(R1-Pad1)") (class "Default")
      (node (ref "R1") (pin "1") (pinfunction "1_1") (pintype "passive"))
      (node (ref "R2") (pin "2") (pinfunction "2_2") (pintype "passive"))
    )
    (net (code "30") (name "Net-(R18-Pad2)") (class "Default")
      (node (ref "R18") (pin "2") (pinfunction "2_2") (pintype "passive"))
      (node (ref "U10") (pin "2") (pinfunction "RFIN_2") (pintype "input"))
      (node (ref "U10") (pin "3") (pinfunction "RFIN_3") (pintype "input"))
      (node (ref "U10") (pin "4") (pinfunction "RFIN_4") (pintype "input"))
    )
    (net (code "31") (name "Net-(SW1-P)") (class "Default")
      (node (ref "SW1") (pin "2") (pinfunction "P_2") (pintype "passive"))
      (node (ref "U1") (pin "1") (pinfunction "A_1") (pintype "input"))
    )
    (net (code "32") (name "Net-(SW1-S)") (class "Default")
      (node (ref "R5") (pin "1") (pinfunction "1_1") (pintype "passive"))
      (node (ref "SW1") (pin "3") (pinfunction "S_3") (pintype "passive"))
    )
    (net (code "33") (name "Net-(U1-B)") (class "Default")
      (node (ref "U1") (pin "2") (pinfunction "B_2") (pintype "input"))
      (node (ref "U11") (pin "4") (pinfunction "Y_4") (pintype "bidirectional"))
    )
    (net (code "34") (name "Net-(U2-SET)") (class "Default")
      (node (ref "R11") (pin "2") (pinfunction "2_2") (pintype "passive"))
      (node (ref "U2") (pin "3") (pinfunction "SET_3") (pintype "input"))
    )
    (net (code "35") (name "Net-(U3-SET)") (class "Default")
      (node (ref "R12") (pin "2") (pinfunction "2_2") (pintype "passive"))
      (node (ref "U3") (pin "3") (pinfunction "SET_3") (pintype "input"))
    )
    (net (code "36") (name "Net-(U4-IN)") (class "Default")
      (node (ref "C26") (pin "2") (pinfunction "2_2") (pintype "passive"))
      (node (ref "U4") (pin "2") (pinfunction "IN_2") (pintype "input"))
    )
    (net (code "37") (name "Net-(U4-OUT)") (class "Default")
      (node (ref "C28") (pin "1") (pinfunction "1_1") (pintype "passive"))
      (node (ref "L4") (pin "1") (pinfunction "1_1") (pintype "bidirectional"))
      (node (ref "U4") (pin "7") (pinfunction "OUT_7") (pintype "output"))
    )
    (net (code "38") (name "Net-(U4-SHTDN)") (class "Default")
      (node (ref "R30") (pin "1") (pinfunction "1_1") (pintype "passive"))
      (node (ref "R31") (pin "1") (pinfunction "1_1") (pintype "passive"))
      (node (ref "U4") (pin "6") (pinfunction "SHTDN_6") (pintype "input"))
      (node (ref "U5") (pin "6") (pinfunction "SHTDN_6") (pintype "input"))
    )
    (net (code "39") (name "Net-(U5-IN)") (class "Default")
      (node (ref "C1") (pin "2") (pinfunction "2_2") (pintype "passive"))
      (node (ref "U5") (pin "2") (pinfunction "IN_2") (pintype "input"))
    )
    (net (code "40") (name "Net-(U5-OUT)") (class "Default")
      (node (ref "C3") (pin "1") (pinfunction "1_1") (pintype "passive"))
      (node (ref "L5") (pin "1") (pinfunction "1_1") (pintype "bidirectional"))
      (node (ref "U5") (pin "7") (pinfunction "OUT_7") (pintype "output"))
    )
    (net (code "41") (name "Net-(U7-CTRL)") (class "Default")
      (node (ref "C11") (pin "1") (pinfunction "1_1") (pintype "passive"))
      (node (ref "R21") (pin "2") (pinfunction "2_2") (pintype "passive"))
      (node (ref "R22") (pin "1") (pinfunction "1_1") (pintype "passive"))
      (node (ref "U7") (pin "5") (pinfunction "CTRL_5") (pintype "bidirectional"))
    )
    (net (code "42") (name "Net-(U7-EN)") (class "Default")
      (node (ref "C12") (pin "1") (pinfunction "1_1") (pintype "passive"))
      (node (ref "R15") (pin "2") (pinfunction "2_2") (pintype "passive"))
      (node (ref "R16") (pin "1") (pinfunction "1_1") (pintype "passive"))
      (node (ref "U7") (pin "6") (pinfunction "EN_6") (pintype "bidirectional"))
    )
    (net (code "43") (name "Net-(U8-CTRL)") (class "Default")
      (node (ref "C32") (pin "1") (pinfunction "1_1") (pintype "passive"))
      (node (ref "R26") (pin "2") (pinfunction "2_2") (pintype "passive"))
      (node (ref "R27") (pin "1") (pinfunction "1_1") (pintype "passive"))
      (node (ref "U8") (pin "5") (pinfunction "CTRL_5") (pintype "bidirectional"))
    )
    (net (code "44") (name "Net-(U8-EN)") (class "Default")
      (node (ref "C33") (pin "1") (pinfunction "1_1") (pintype "passive"))
      (node (ref "R24") (pin "2") (pinfunction "2_2") (pintype "passive"))
      (node (ref "R25") (pin "1") (pinfunction "1_1") (pintype "passive"))
      (node (ref "U8") (pin "6") (pinfunction "EN_6") (pintype "bidirectional"))
    )
    (net (code "45") (name "Net-(U10-IREF2)") (class "Default")
      (node (ref "C18") (pin "1") (pinfunction "1_1") (pintype "passive"))
      (node (ref "R19") (pin "2") (pinfunction "2_2") (pintype "passive"))
      (node (ref "U10") (pin "8") (pinfunction "IREF2_8") (pintype "passive"))
    )
    (net (code "46") (name "Net-(U10-VBIAS)") (class "Default")
      (node (ref "R20") (pin "1") (pinfunction "1_1") (pintype "passive"))
      (node (ref "U10") (pin "16") (pinfunction "VBIAS_16") (pintype "power_in"))
    )
    (net (code "47") (name "Net-(U10-VCC1)") (class "Default")
      (node (ref "L2") (pin "1") (pinfunction "1_1") (pintype "bidirectional"))
      (node (ref "U10") (pin "20") (pinfunction "VCC1_20") (pintype "power_in"))
    )
    (net (code "48") (name "Net-(U10-VCC2)") (class "Default")
      (node (ref "L1") (pin "1") (pinfunction "1_1") (pintype "bidirectional"))
      (node (ref "U10") (pin "18") (pinfunction "VCC2_18") (pintype "power_in"))
    )
    (net (code "49") (name "PA_MATCH_OUT") (class "Default")
      (node (ref "C20") (pin "2") (pinfunction "2_2") (pintype "passive"))
      (node (ref "U8") (pin "4") (pinfunction "RF1_4") (pintype "bidirectional"))
    )
    (net (code "50") (name "PA_ON_LNA_OFF") (class "Default")
      (node (ref "R19") (pin "1") (pinfunction "1_1") (pintype "passive"))
      (node (ref "U10") (pin "6") (pinfunction "IREF1_6") (pintype "passive"))
      (node (ref "U12") (pin "1") (pinfunction "A_1") (pintype "input"))
      (node (ref "U2") (pin "6") (pinfunction "OUT_6") (pintype "output"))
    )
    (net (code "51") (name "RX_IN") (class "Default")
      (node (ref "FL1") (pin "1") (pinfunction "IN_1") (pintype "passive"))
      (node (ref "U8") (pin "8") (pinfunction "RF2_8") (pintype "bidirectional"))
    )
    (net (code "52") (name "TX_RX_COMMON") (class "Default")
      (node (ref "U7") (pin "2") (pinfunction "RF_COM_2") (pintype "bidirectional"))
      (node (ref "U8") (pin "2") (pinfunction "RF_COM_2") (pintype "bidirectional"))
    )
    (net (code "53") (name "TX_RX_CTL") (class "Default")
      (node (ref "R26") (pin "1") (pinfunction "1_1") (pintype "passive"))
      (node (ref "U3") (pin "6") (pinfunction "OUT_6") (pintype "output"))
    )
  )
)
